# STM32F429IGT6.net
KiCad netlist of a schematic drawn in Altium Designer
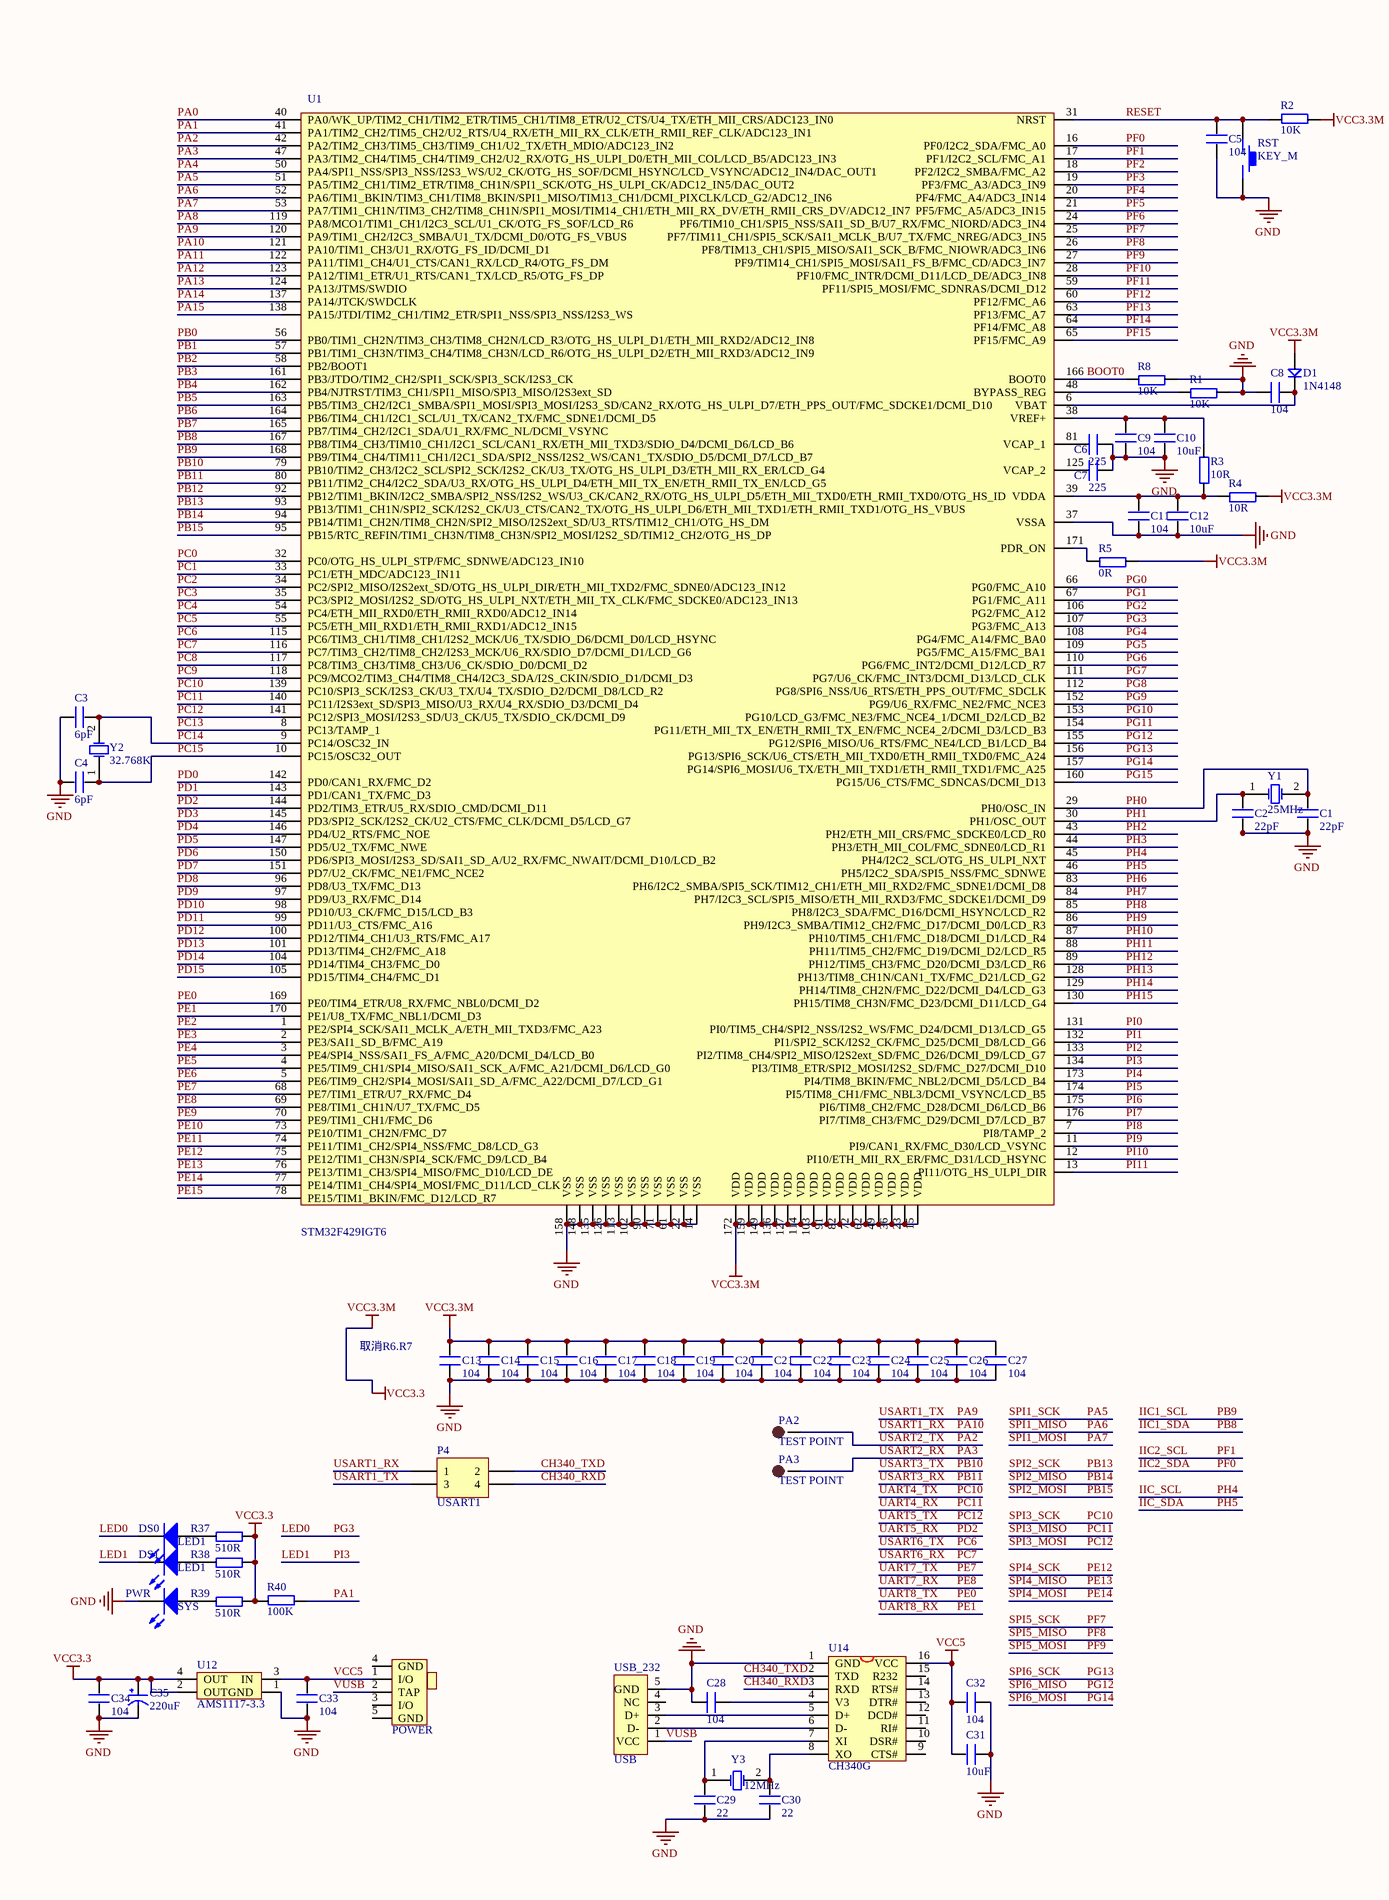
[diagram p0: STM32F429IGT6.SchDoc, left]
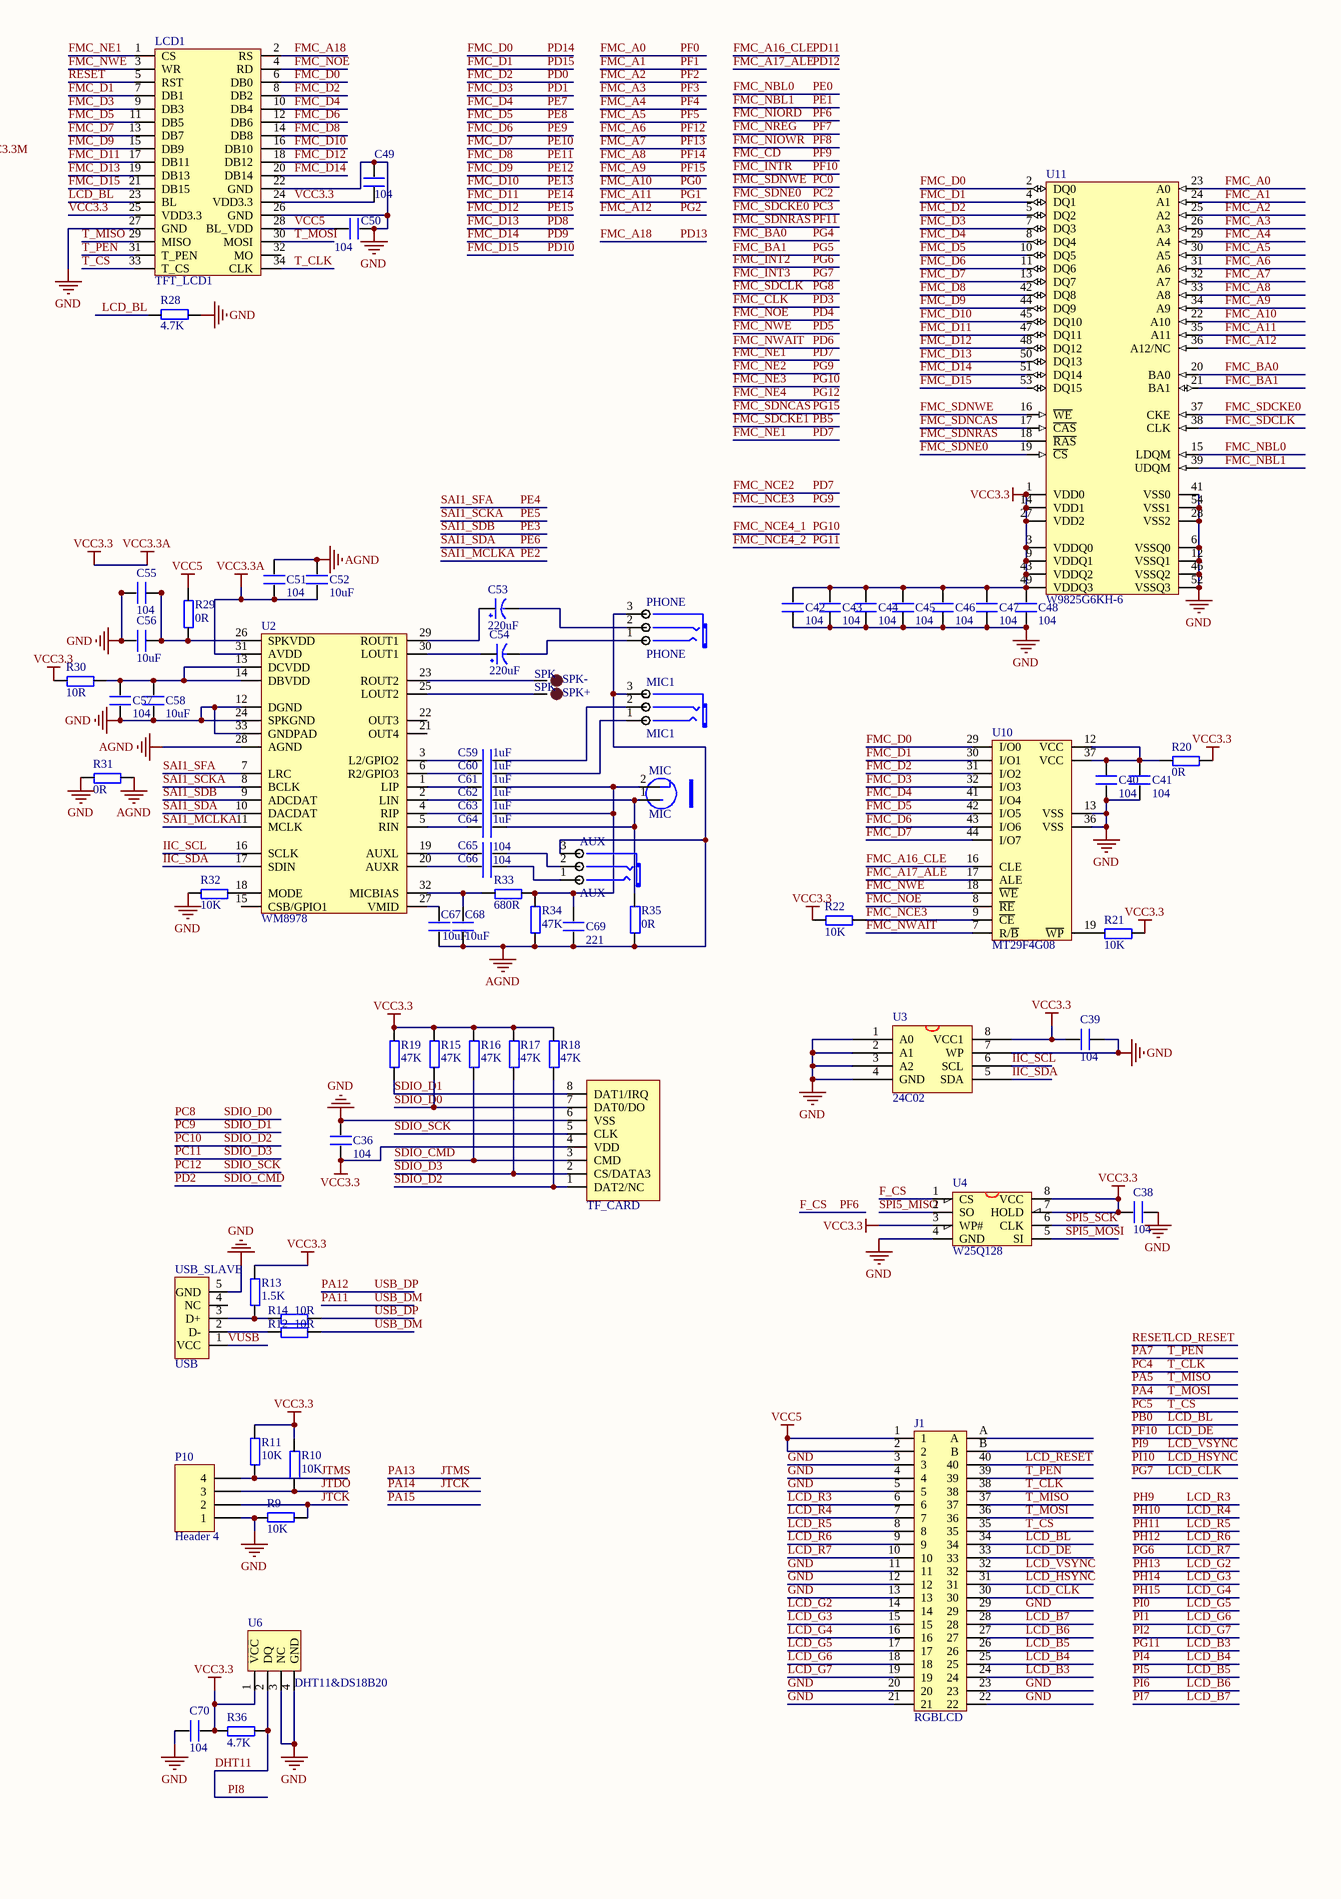
[diagram p1: STM32F429IGT6.SchDoc, right]

(export (version "E")
  (design (tool "Eeschema 10.0.6"))
  (components
    (comp (ref "AUX")
      (value "AUX")
      (footprint "PHONE_ST")
      (libsource (lib "阿波罗STM32F4&F7&H7底板封装库") (part "PHONE_M"))
    )
    (comp (ref "C1")
      (value "22pF")
      (footprint "C 0603_M")
      (libsource (lib "WarShip V3 STM32103封装库") (part "C"))
    )
    (comp (ref "C2")
      (value "22pF")
      (footprint "C 0603_M")
      (libsource (lib "WarShip V3 STM32103封装库") (part "C"))
    )
    (comp (ref "C3")
      (value "6pF")
      (footprint "C 0603_M")
      (libsource (lib "WarShip V3 STM32103封装库") (part "C"))
    )
    (comp (ref "C4")
      (value "6pF")
      (footprint "C 0603_M")
      (libsource (lib "WarShip V3 STM32103封装库") (part "C"))
    )
    (comp (ref "C5")
      (value "104")
      (footprint "C 0603_M")
      (libsource (lib "WarShip V3 STM32103封装库") (part "C"))
    )
    (comp (ref "C6") (value "225") (footprint "C 0603_M") (libsource (lib "阿波罗STM32F4&F7底板封装库") (part "C")))
    (comp (ref "C7") (value "225") (footprint "C 0603_M") (libsource (lib "阿波罗STM32F4&F7底板封装库") (part "C")))
    (comp (ref "C8") (value "104") (footprint "C 0603_M") (libsource (lib "阿波罗STM32F4&F7底板封装库") (part "C")))
    (comp (ref "C9") (value "104") (footprint "C 0603_M") (libsource (lib "阿波罗STM32F4&F7底板封装库") (part "C")))
    (comp (ref "C10") (value "10uF") (footprint "C 0603_M") (libsource (lib "阿波罗STM32F4&F7底板封装库") (part "C")))
    (comp (ref "C11") (value "104") (footprint "C 0603_M") (libsource (lib "阿波罗STM32F4&F7底板封装库") (part "C")))
    (comp (ref "C12") (value "10uF") (footprint "C 0603_M") (libsource (lib "阿波罗STM32F4&F7底板封装库") (part "C")))
    (comp (ref "C13") (value "104") (footprint "C 0603_M") (libsource (lib "STM32F429核心板封装库") (part "C")))
    (comp (ref "C14") (value "104") (footprint "C 0603_M") (libsource (lib "STM32F429核心板封装库") (part "C")))
    (comp (ref "C15") (value "104") (footprint "C 0603_M") (libsource (lib "STM32F429核心板封装库") (part "C")))
    (comp (ref "C16") (value "104") (footprint "C 0603_M") (libsource (lib "STM32F429核心板封装库") (part "C")))
    (comp (ref "C17") (value "104") (footprint "C 0603_M") (libsource (lib "STM32F429核心板封装库") (part "C")))
    (comp (ref "C18") (value "104") (footprint "C 0603_M") (libsource (lib "STM32F429核心板封装库") (part "C")))
    (comp (ref "C19") (value "104") (footprint "C 0603_M") (libsource (lib "STM32F429核心板封装库") (part "C")))
    (comp (ref "C20") (value "104") (footprint "C 0603_M") (libsource (lib "STM32F429核心板封装库") (part "C")))
    (comp (ref "C21") (value "104") (footprint "C 0603_M") (libsource (lib "STM32F429核心板封装库") (part "C")))
    (comp (ref "C22") (value "104") (footprint "C 0603_M") (libsource (lib "STM32F429核心板封装库") (part "C")))
    (comp (ref "C23") (value "104") (footprint "C 0603_M") (libsource (lib "STM32F429核心板封装库") (part "C")))
    (comp (ref "C24") (value "104") (footprint "C 0603_M") (libsource (lib "STM32F429核心板封装库") (part "C")))
    (comp (ref "C25") (value "104") (footprint "C 0603_M") (libsource (lib "STM32F429核心板封装库") (part "C")))
    (comp (ref "C26") (value "104") (footprint "C 0603_M") (libsource (lib "STM32F429核心板封装库") (part "C")))
    (comp (ref "C27") (value "104") (footprint "C 0603_M") (libsource (lib "STM32F429核心板封装库") (part "C")))
    (comp (ref "C28")
      (value "104")
      (footprint "C 0603_M")
      (libsource (lib "WarShip V3 STM32103封装库") (part "C"))
    )
    (comp (ref "C29")
      (value "22")
      (footprint "C 0603_M")
      (libsource (lib "WarShip V3 STM32103封装库") (part "C"))
    )
    (comp (ref "C30")
      (value "22")
      (footprint "C 0603_M")
      (libsource (lib "WarShip V3 STM32103封装库") (part "C"))
    )
    (comp (ref "C31")
      (value "10uF")
      (footprint "C 0603_M")
      (libsource (lib "WarShip V3 STM32103封装库") (part "C"))
    )
    (comp (ref "C32")
      (value "104")
      (footprint "C 0603_M")
      (libsource (lib "WarShip V3 STM32103封装库") (part "C"))
    )
    (comp (ref "C33")
      (value "104")
      (footprint "C 0603_M")
      (libsource (lib "WarShip V3 STM32103封装库") (part "C"))
    )
    (comp (ref "C34")
      (value "104")
      (footprint "C 0603_M")
      (libsource (lib "WarShip V3 STM32103封装库") (part "C"))
    )
    (comp (ref "C35")
      (value "220uF")
      (footprint "CT 6*6 - C")
      (libsource (lib "WarShip V3 STM32103封装库") (part "CAP"))
    )
    (comp (ref "C36")
      (value "104")
      (footprint "C 0603_M")
      (libsource (lib "WarShip V3 STM32103封装库") (part "C"))
    )
    (comp (ref "C38")
      (value "104")
      (footprint "C 0603_M")
      (libsource (lib "WarShip V3 STM32103封装库") (part "C"))
    )
    (comp (ref "C39")
      (value "104")
      (footprint "C 0603_M")
      (libsource (lib "WarShip V3 STM32103封装库") (part "C"))
    )
    (comp (ref "C40")
      (value "104")
      (footprint "C 0603_M")
      (libsource (lib "WarShip V3 STM32103封装库") (part "C"))
    )
    (comp (ref "C41")
      (value "104")
      (footprint "C 0603_M")
      (libsource (lib "WarShip V3 STM32103封装库") (part "C"))
    )
    (comp (ref "C42")
      (value "104")
      (footprint "C 0603_M")
      (libsource (lib "WarShip V3 STM32103封装库") (part "C"))
    )
    (comp (ref "C43")
      (value "104")
      (footprint "C 0603_M")
      (libsource (lib "WarShip V3 STM32103封装库") (part "C"))
    )
    (comp (ref "C44")
      (value "104")
      (footprint "C 0603_M")
      (libsource (lib "WarShip V3 STM32103封装库") (part "C"))
    )
    (comp (ref "C45")
      (value "104")
      (footprint "C 0603_M")
      (libsource (lib "WarShip V3 STM32103封装库") (part "C"))
    )
    (comp (ref "C46")
      (value "104")
      (footprint "C 0603_M")
      (libsource (lib "WarShip V3 STM32103封装库") (part "C"))
    )
    (comp (ref "C47")
      (value "104")
      (footprint "C 0603_M")
      (libsource (lib "WarShip V3 STM32103封装库") (part "C"))
    )
    (comp (ref "C48")
      (value "104")
      (footprint "C 0603_M")
      (libsource (lib "WarShip V3 STM32103封装库") (part "C"))
    )
    (comp (ref "C49") (value "104") (footprint "C 0603_M") (libsource (lib "MYCOMLIB") (part "C")))
    (comp (ref "C50") (value "104") (footprint "C 0603_M") (libsource (lib "MYCOMLIB") (part "C")))
    (comp (ref "C51") (value "104") (footprint "C 0603_M") (libsource (lib "阿波罗STM32F4&F7底板封装库") (part "C")))
    (comp (ref "C52") (value "10uF") (footprint "C 0603_M") (libsource (lib "阿波罗STM32F4&F7底板封装库") (part "C")))
    (comp (ref "C53")
      (value "220uF")
      (footprint "cc4*5.4")
      (libsource (lib "阿波罗STM32F4&F7底板封装库") (part "CAP"))
    )
    (comp (ref "C54")
      (value "220uF")
      (footprint "cc4*5.4")
      (libsource (lib "阿波罗STM32F4&F7底板封装库") (part "CAP"))
    )
    (comp (ref "C55") (value "104") (footprint "C 0603_M") (libsource (lib "阿波罗STM32F4&F7底板封装库") (part "C")))
    (comp (ref "C56") (value "10uF") (footprint "C 0603_M") (libsource (lib "阿波罗STM32F4&F7底板封装库") (part "C")))
    (comp (ref "C57") (value "104") (footprint "C 0603_M") (libsource (lib "阿波罗STM32F4&F7底板封装库") (part "C")))
    (comp (ref "C58") (value "10uF") (footprint "C 0603_M") (libsource (lib "阿波罗STM32F4&F7底板封装库") (part "C")))
    (comp (ref "C59") (value "1uF") (footprint "C 0603_M") (libsource (lib "阿波罗STM32F4&F7底板封装库") (part "C")))
    (comp (ref "C60") (value "1uF") (footprint "C 0603_M") (libsource (lib "阿波罗STM32F4&F7底板封装库") (part "C")))
    (comp (ref "C61") (value "1uF") (footprint "C 0603_M") (libsource (lib "阿波罗STM32F4&F7底板封装库") (part "C")))
    (comp (ref "C62") (value "1uF") (footprint "C 0603_M") (libsource (lib "阿波罗STM32F4&F7底板封装库") (part "C")))
    (comp (ref "C63") (value "1uF") (footprint "C 0603_M") (libsource (lib "阿波罗STM32F4&F7底板封装库") (part "C")))
    (comp (ref "C64") (value "1uF") (footprint "C 0603_M") (libsource (lib "阿波罗STM32F4&F7底板封装库") (part "C")))
    (comp (ref "C65") (value "104") (footprint "C 0603_M") (libsource (lib "阿波罗STM32F4&F7底板封装库") (part "C")))
    (comp (ref "C66") (value "104") (footprint "C 0603_M") (libsource (lib "阿波罗STM32F4&F7底板封装库") (part "C")))
    (comp (ref "C67") (value "10uF") (footprint "C 0603_M") (libsource (lib "阿波罗STM32F4&F7底板封装库") (part "C")))
    (comp (ref "C68") (value "10uF") (footprint "C 0603_M") (libsource (lib "阿波罗STM32F4&F7底板封装库") (part "C")))
    (comp (ref "C69") (value "221") (footprint "C 0603_M") (libsource (lib "阿波罗STM32F4&F7底板封装库") (part "C")))
    (comp (ref "C70")
      (value "104")
      (footprint "C 0603_M")
      (libsource (lib "WarShip V3 STM32103封装库") (part "C"))
    )
    (comp (ref "D1")
      (value "1N4148")
      (footprint "DIODE_SOP")
      (libsource (lib "WarShip V3 STM32103封装库") (part "D"))
    )
    (comp (ref "DS0")
      (value "LED1")
      (footprint "SMDLED")
      (description "Typical RED, GREEN, YELLOW, AMBER GaAs LED")
      (fields (field (name "PUBLISHER") "Altium Limited"))
      (libsource (lib "Miscellaneous Devices") (part "LED2"))
    )
    (comp (ref "DS1")
      (value "LED1")
      (footprint "SMDLED")
      (description "Typical RED, GREEN, YELLOW, AMBER GaAs LED")
      (fields (field (name "PUBLISHER") "Altium Limited"))
      (libsource (lib "Miscellaneous Devices") (part "LED2"))
    )
    (comp (ref "J1")
      (value "RGBLCD")
      (footprint "FPC-TOP40")
      (description "FPC-40P-0.5mm")
      (libsource (lib "STM32F429核心板封装库") (part "FPC-40"))
    )
    (comp (ref "LCD1")
      (value "TFT_LCD1")
      (footprint "DB2*17-3.5")
      (libsource (lib "3.5TFTLCD封装库") (part "TFT_LCD2"))
    )
    (comp (ref "MIC")
      (value "MIC")
      (footprint "MIC-6022")
      (libsource (lib "阿波罗STM32F4&F7&H7底板封装库") (part "MIC"))
    )
    (comp (ref "MIC1")
      (value "MIC1")
      (footprint "PHONE_ST")
      (libsource (lib "阿波罗STM32F4&F7&H7底板封装库") (part "PHONE_M"))
    )
    (comp (ref "P4")
      (value "USART1")
      (footprint "HDR2.54-LI-2x2P")
      (description "Header, 2-Pin, Dual row")
      (fields (field (name "PUBLISHER") "Altium Limited"))
      (libsource (lib "WarShip V3 STM32103封装库") (part "Header 2X2"))
    )
    (comp (ref "P10")
      (value "Header 4")
      (footprint "HDR2.54-LI-4P")
      (description "Header, 4-Pin")
      (fields (field (name "PUBLISHER") "Altium Limited"))
      (libsource (lib "WarShip V3 STM32103封装库") (part "Header 4"))
    )
    (comp (ref "PA2")
      (value "TEST POINT")
      (footprint "TP-1.5")
      (description "测试点")
      (libsource (lib "STM32F429核心板封装库") (part "TEST-POINT"))
    )
    (comp (ref "PA3")
      (value "TEST POINT")
      (footprint "TP-1.5")
      (description "测试点")
      (libsource (lib "STM32F429核心板封装库") (part "TEST-POINT"))
    )
    (comp (ref "PHONE")
      (value "PHONE")
      (footprint "PHONE_ST")
      (libsource (lib "阿波罗STM32F4&F7&H7底板封装库") (part "PHONE_M"))
    )
    (comp (ref "POWER")
      (value "BUTTON_DIP3")
      (footprint "BTN8.8*4.6")
      (description "拨动开关SS-12F44")
      (libsource (lib "Pandora_STM32L4_Board_V2.4") (part "BUTTON_DIP3"))
    )
    (comp (ref "PWR")
      (value "SYS")
      (footprint "SMDLED")
      (description "Typical RED, GREEN, YELLOW, AMBER GaAs LED")
      (fields (field (name "PUBLISHER") "Altium Limited"))
      (libsource (lib "Miscellaneous Devices") (part "LED2"))
    )
    (comp (ref "R1") (value "10K") (footprint "R 0603_M") (libsource (lib "阿波罗STM32F4&F7底板封装库") (part "R")))
    (comp (ref "R2")
      (value "10K")
      (footprint "R 0603_M")
      (libsource (lib "WarShip V3 STM32103封装库") (part "R"))
    )
    (comp (ref "R3") (value "10R") (footprint "R 0603_M") (libsource (lib "阿波罗STM32F4&F7底板封装库") (part "R")))
    (comp (ref "R4") (value "10R") (footprint "R 0603_M") (libsource (lib "阿波罗STM32F4&F7底板封装库") (part "R")))
    (comp (ref "R5") (value "0R") (footprint "R 0603_M") (libsource (lib "阿波罗STM32F4&F7底板封装库") (part "R")))
    (comp (ref "R8") (value "10K") (footprint "R 0603_M") (libsource (lib "阿波罗STM32F4&F7底板封装库") (part "R")))
    (comp (ref "R9")
      (value "10K")
      (footprint "R 0603_M")
      (libsource (lib "WarShip V3 STM32103封装库") (part "R"))
    )
    (comp (ref "R10")
      (value "10K")
      (footprint "R 0603_M")
      (libsource (lib "WarShip V3 STM32103封装库") (part "R"))
    )
    (comp (ref "R11")
      (value "10K")
      (footprint "R 0603_M")
      (libsource (lib "WarShip V3 STM32103封装库") (part "R"))
    )
    (comp (ref "R12")
      (value "10R")
      (footprint "R 0603_M")
      (libsource (lib "WarShip V3 STM32103封装库") (part "R"))
    )
    (comp (ref "R13")
      (value "1.5K")
      (footprint "R 0603_M")
      (libsource (lib "WarShip V3 STM32103封装库") (part "R"))
    )
    (comp (ref "R14")
      (value "10R")
      (footprint "R 0603_M")
      (libsource (lib "WarShip V3 STM32103封装库") (part "R"))
    )
    (comp (ref "R15")
      (value "47K")
      (footprint "R 0603_M")
      (libsource (lib "WarShip V3 STM32103封装库") (part "R"))
    )
    (comp (ref "R16")
      (value "47K")
      (footprint "R 0603_M")
      (libsource (lib "WarShip V3 STM32103封装库") (part "R"))
    )
    (comp (ref "R17")
      (value "47K")
      (footprint "R 0603_M")
      (libsource (lib "WarShip V3 STM32103封装库") (part "R"))
    )
    (comp (ref "R18")
      (value "47K")
      (footprint "R 0603_M")
      (libsource (lib "WarShip V3 STM32103封装库") (part "R"))
    )
    (comp (ref "R19")
      (value "47K")
      (footprint "R 0603_M")
      (libsource (lib "WarShip V3 STM32103封装库") (part "R"))
    )
    (comp (ref "R20")
      (value "0R")
      (footprint "R 0603_M")
      (libsource (lib "WarShip V3 STM32103封装库") (part "R"))
    )
    (comp (ref "R21")
      (value "10K")
      (footprint "R 0603_M")
      (libsource (lib "WarShip V3 STM32103封装库") (part "R"))
    )
    (comp (ref "R22")
      (value "10K")
      (footprint "R 0603_M")
      (libsource (lib "WarShip V3 STM32103封装库") (part "R"))
    )
    (comp (ref "R28") (value "4.7K") (footprint "R 0603_M") (libsource (lib "MYCOMLIB") (part "R")))
    (comp (ref "R29") (value "0R") (footprint "R 0603_M") (libsource (lib "阿波罗STM32F4&F7底板封装库") (part "R")))
    (comp (ref "R30") (value "10R") (footprint "R 0603_M") (libsource (lib "阿波罗STM32F4&F7底板封装库") (part "R")))
    (comp (ref "R31") (value "0R") (footprint "R 0603_M") (libsource (lib "阿波罗STM32F4&F7底板封装库") (part "R")))
    (comp (ref "R32") (value "10K") (footprint "R 0603_M") (libsource (lib "阿波罗STM32F4&F7底板封装库") (part "R")))
    (comp (ref "R33") (value "680R") (footprint "R 0603_M") (libsource (lib "阿波罗STM32F4&F7底板封装库") (part "R")))
    (comp (ref "R34") (value "47K") (footprint "R 0603_M") (libsource (lib "阿波罗STM32F4&F7底板封装库") (part "R")))
    (comp (ref "R35") (value "0R") (footprint "R 0603_M") (libsource (lib "阿波罗STM32F4&F7底板封装库") (part "R")))
    (comp (ref "R36")
      (value "4.7K")
      (footprint "R 0603_M")
      (libsource (lib "WarShip V3 STM32103封装库") (part "R"))
    )
    (comp (ref "R37") (value "510R") (footprint "R 0603_M") (libsource (lib "MYCOMLIB") (part "R")))
    (comp (ref "R38") (value "510R") (footprint "R 0603_M") (libsource (lib "MYCOMLIB") (part "R")))
    (comp (ref "R39") (value "510R") (footprint "R 0603_M") (libsource (lib "MYCOMLIB") (part "R")))
    (comp (ref "R40") (value "100K") (footprint "R 0603_M") (libsource (lib "MYCOMLIB") (part "R")))
    (comp (ref "RST")
      (value "KEY_M")
      (footprint "TSW SMD-3*6*2.5")
      (libsource (lib "STM32F429核心板封装库") (part "KEY_M"))
    )
    (comp (ref "SPK+")
      (value "SPK")
      (footprint "TP-1.5")
      (description "测试点")
      (libsource (lib "STM32F429核心板封装库") (part "TEST-POINT"))
    )
    (comp (ref "SPK-")
      (value "SPK")
      (footprint "TP-1.5")
      (description "测试点")
      (libsource (lib "STM32F429核心板封装库") (part "TEST-POINT"))
    )
    (comp (ref "TF_CARD")
      (value "SD-MICRO-TF")
      (footprint "SD-MICRO-TF")
      (description "SD,MICRO,TF")
      (libsource (lib "Pandora_STM32L4_Board_V2.4") (part "SD-MICRO-TF"))
    )
    (comp (ref "U1")
      (value "STM32F429IGT6")
      (footprint "LQFP176")
      (libsource (lib "STM32F429核心板封装库") (part "STM32F429IGT6"))
    )
    (comp (ref "U2")
      (value "WM8978")
      (footprint "qfn32")
      (description "24bit ADC&DAC")
      (libsource (lib "STM32H743") (part "WM8978"))
    )
    (comp (ref "U3")
      (value "24C02")
      (footprint "SOP8_M")
      (libsource (lib "WarShip V3 STM32103封装库") (part "24C256"))
    )
    (comp (ref "U4")
      (value "W25Q128")
      (footprint "SOIC-8")
      (description "W25X16;SST25VF016;MX25L1605")
      (libsource (lib "WarShip V3 STM32103封装库") (part "W25X16"))
    )
    (comp (ref "U6")
      (value "DHT11&DS18B20")
      (footprint "DHT11")
      (description "数字温湿度传感器")
      (libsource (lib "WarShip V3 STM32103封装库") (part "DHT11"))
    )
    (comp (ref "U10")
      (value "MT29F4G08")
      (footprint "TSOP48")
      (description "256MB NAND FLASH")
      (libsource (lib "STM32F429核心板封装库") (part "K9F2G08U0C"))
    )
    (comp (ref "U11")
      (value "W9825G6KH-6")
      (footprint "TSOP54")
      (description "32MB SDRAM")
      (libsource (lib "STM32F429核心板封装库") (part "IS42S16160B"))
    )
    (comp (ref "U12")
      (value "AMS1117-3.3")
      (footprint "AMS1117")
      (libsource (lib "WarShip V3 STM32103封装库") (part "AMS1117"))
    )
    (comp (ref "U14")
      (value "CH340G")
      (footprint "SOP16_M")
      (description "USB2UART")
      (libsource (lib "WarShip V3 STM32103封装库") (part "CH340G"))
    )
    (comp (ref "USB_232")
      (value "USB")
      (footprint "USB-MINI-A")
      (libsource (lib "WarShip V3 STM32103封装库") (part "USB5"))
    )
    (comp (ref "USB_SLAVE")
      (value "USB")
      (footprint "USB-MINI-A")
      (libsource (lib "WarShip V3 STM32103封装库") (part "USB5"))
    )
    (comp (ref "Y1")
      (value "25MHz")
      (footprint "OSC HC-49S")
      (description "Crystal Oscillator")
      (fields (field (name "PUBLISHER") "Altium Limited"))
      (libsource (lib "WarShip V3 STM32103封装库") (part "XTAL"))
    )
    (comp (ref "Y2")
      (value "32.768K")
      (footprint "OSC-2x6-WI-A")
      (description "Crystal Oscillator")
      (fields (field (name "PUBLISHER") "Altium Limited"))
      (libsource (lib "WarShip V3 STM32103封装库") (part "XTAL"))
    )
    (comp (ref "Y3")
      (value "12MHz")
      (footprint "OSC HC-49S")
      (description "Crystal Oscillator")
      (fields (field (name "PUBLISHER") "Altium Limited"))
      (libsource (lib "WarShip V3 STM32103封装库") (part "XTAL"))
    )
  )
  (nets
    (net (code "1") (name "/BOOT0") (class "Default")
      (node (ref "R8") (pin "1") (pintype "passive"))
      (node (ref "U1") (pin "166") (pinfunction "BOOT0_166") (pintype "passive"))
    )
    (net (code "2") (name "/CH340_RXD") (class "Default")
      (node (ref "P4") (pin "4") (pinfunction "4_4") (pintype "passive"))
      (node (ref "U14") (pin "3") (pinfunction "RXD_3") (pintype "passive"))
    )
    (net (code "3") (name "/CH340_TXD") (class "Default")
      (node (ref "P4") (pin "2") (pinfunction "2_2") (pintype "passive"))
      (node (ref "U14") (pin "2") (pinfunction "TXD_2") (pintype "passive"))
    )
    (net (code "4") (name "/DHT11") (class "Default")
      (node (ref "R36") (pin "2") (pintype "passive"))
      (node (ref "U1") (pin "7") (pinfunction "PI8/TAMP_2_7") (pintype "passive"))
      (node (ref "U6") (pin "2") (pinfunction "DQ_2") (pintype "passive"))
    )
    (net (code "5") (name "/FMC_A0") (class "Default")
      (node (ref "U1") (pin "16") (pinfunction "PF0/I2C2_SDA/FMC_A0_16") (pintype "passive"))
      (node (ref "U11") (pin "23") (pinfunction "A0_23") (pintype "input"))
    )
    (net (code "6") (name "/FMC_A1") (class "Default")
      (node (ref "U1") (pin "17") (pinfunction "PF1/I2C2_SCL/FMC_A1_17") (pintype "passive"))
      (node (ref "U11") (pin "24") (pinfunction "A1_24") (pintype "input"))
    )
    (net (code "7") (name "/FMC_A2") (class "Default")
      (node (ref "U1") (pin "18") (pinfunction "PF2/I2C2_SMBA/FMC_A2_18") (pintype "passive"))
      (node (ref "U11") (pin "25") (pinfunction "A2_25") (pintype "input"))
    )
    (net (code "8") (name "/FMC_A3") (class "Default")
      (node (ref "U1") (pin "19") (pinfunction "PF3/FMC_A3/ADC3_IN9_19") (pintype "passive"))
      (node (ref "U11") (pin "26") (pinfunction "A3_26") (pintype "input"))
    )
    (net (code "9") (name "/FMC_A4") (class "Default")
      (node (ref "U1") (pin "20") (pinfunction "PF4/FMC_A4/ADC3_IN14_20") (pintype "passive"))
      (node (ref "U11") (pin "29") (pinfunction "A4_29") (pintype "input"))
    )
    (net (code "10") (name "/FMC_A5") (class "Default")
      (node (ref "U1") (pin "21") (pinfunction "PF5/FMC_A5/ADC3_IN15_21") (pintype "passive"))
      (node (ref "U11") (pin "30") (pinfunction "A5_30") (pintype "input"))
    )
    (net (code "11") (name "/FMC_A6") (class "Default")
      (node (ref "U1") (pin "60") (pinfunction "PF12/FMC_A6_60") (pintype "passive"))
      (node (ref "U11") (pin "31") (pinfunction "A6_31") (pintype "input"))
    )
    (net (code "12") (name "/FMC_A7") (class "Default")
      (node (ref "U1") (pin "63") (pinfunction "PF13/FMC_A7_63") (pintype "passive"))
      (node (ref "U11") (pin "32") (pinfunction "A7_32") (pintype "input"))
    )
    (net (code "13") (name "/FMC_A8") (class "Default")
      (node (ref "U1") (pin "64") (pinfunction "PF14/FMC_A8_64") (pintype "passive"))
      (node (ref "U11") (pin "33") (pinfunction "A8_33") (pintype "input"))
    )
    (net (code "14") (name "/FMC_A9") (class "Default")
      (node (ref "U1") (pin "65") (pinfunction "PF15/FMC_A9_65") (pintype "passive"))
      (node (ref "U11") (pin "34") (pinfunction "A9_34") (pintype "input"))
    )
    (net (code "15") (name "/FMC_A10") (class "Default")
      (node (ref "U1") (pin "66") (pinfunction "PG0/FMC_A10_66") (pintype "passive"))
      (node (ref "U11") (pin "22") (pinfunction "A10_22") (pintype "input"))
    )
    (net (code "16") (name "/FMC_A11") (class "Default")
      (node (ref "U1") (pin "67") (pinfunction "PG1/FMC_A11_67") (pintype "passive"))
      (node (ref "U11") (pin "35") (pinfunction "A11_35") (pintype "input"))
    )
    (net (code "17") (name "/FMC_A12") (class "Default")
      (node (ref "U1") (pin "106") (pinfunction "PG2/FMC_A12_106") (pintype "passive"))
      (node (ref "U11") (pin "36") (pinfunction "A12/NC_36") (pintype "input"))
    )
    (net (code "18") (name "/FMC_A16_CLE") (class "Default")
      (node (ref "U1") (pin "99") (pinfunction "PD11/U3_CTS/FMC_A16_99") (pintype "passive"))
      (node (ref "U10") (pin "16") (pinfunction "CLE_16") (pintype "passive"))
    )
    (net (code "19") (name "/FMC_A17_ALE") (class "Default")
      (node (ref "U1") (pin "100") (pinfunction "PD12/TIM4_CH1/U3_RTS/FMC_A17_100") (pintype "passive"))
      (node (ref "U10") (pin "17") (pinfunction "ALE_17") (pintype "passive"))
    )
    (net (code "20") (name "/FMC_A18") (class "Default")
      (node (ref "LCD1") (pin "2") (pinfunction "RS_2") (pintype "passive"))
      (node (ref "U1") (pin "101") (pinfunction "PD13/TIM4_CH2/FMC_A18_101") (pintype "passive"))
    )
    (net (code "21") (name "/FMC_BA0") (class "Default")
      (node (ref "U1") (pin "108") (pinfunction "PG4/FMC_A14/FMC_BA0_108") (pintype "passive"))
      (node (ref "U11") (pin "20") (pinfunction "BA0_20") (pintype "input"))
    )
    (net (code "22") (name "/FMC_BA1") (class "Default")
      (node (ref "U1") (pin "109") (pinfunction "PG5/FMC_A15/FMC_BA1_109") (pintype "passive"))
      (node (ref "U11") (pin "21") (pinfunction "BA1_21") (pintype "bidirectional"))
    )
    (net (code "23") (name "/FMC_CD") (class "Default")
      (node (ref "U1") (pin "27") (pinfunction "PF9/TIM14_CH1/SPI5_MOSI/SAI1_FS_B/FMC_CD/ADC3_IN7_27") (pintype "passive"))
      (node (ref "U4") (pin "5") (pinfunction "SI_5") (pintype "passive"))
    )
    (net (code "24") (name "/FMC_CLK") (class "Default")
      (node (ref "U1") (pin "145") (pinfunction "PD3/SPI2_SCK/I2S2_CK/U2_CTS/FMC_CLK/DCMI_D5/LCD_G7_145") (pintype "passive"))
    )
    (net (code "25") (name "/FMC_D0") (class "Default")
      (node (ref "LCD1") (pin "6") (pinfunction "DB0_6") (pintype "passive"))
      (node (ref "U1") (pin "104") (pinfunction "PD14/TIM4_CH3/FMC_D0_104") (pintype "passive"))
      (node (ref "U10") (pin "29") (pinfunction "I/O0_29") (pintype "passive"))
      (node (ref "U11") (pin "2") (pinfunction "DQ0_2") (pintype "bidirectional"))
    )
    (net (code "26") (name "/FMC_D1") (class "Default")
      (node (ref "LCD1") (pin "7") (pinfunction "DB1_7") (pintype "passive"))
      (node (ref "U1") (pin "105") (pinfunction "PD15/TIM4_CH4/FMC_D1_105") (pintype "passive"))
      (node (ref "U10") (pin "30") (pinfunction "I/O1_30") (pintype "passive"))
      (node (ref "U11") (pin "4") (pinfunction "DQ1_4") (pintype "bidirectional"))
    )
    (net (code "27") (name "/FMC_D2") (class "Default")
      (node (ref "LCD1") (pin "8") (pinfunction "DB2_8") (pintype "passive"))
      (node (ref "U1") (pin "142") (pinfunction "PD0/CAN1_RX/FMC_D2_142") (pintype "passive"))
      (node (ref "U10") (pin "31") (pinfunction "I/O2_31") (pintype "passive"))
      (node (ref "U11") (pin "5") (pinfunction "DQ2_5") (pintype "bidirectional"))
    )
    (net (code "28") (name "/FMC_D3") (class "Default")
      (node (ref "LCD1") (pin "9") (pinfunction "DB3_9") (pintype "passive"))
      (node (ref "U1") (pin "143") (pinfunction "PD1/CAN1_TX/FMC_D3_143") (pintype "passive"))
      (node (ref "U10") (pin "32") (pinfunction "I/O3_32") (pintype "passive"))
      (node (ref "U11") (pin "7") (pinfunction "DQ3_7") (pintype "bidirectional"))
    )
    (net (code "29") (name "/FMC_D4") (class "Default")
      (node (ref "LCD1") (pin "10") (pinfunction "DB4_10") (pintype "passive"))
      (node (ref "U1") (pin "68") (pinfunction "PE7/TIM1_ETR/U7_RX/FMC_D4_68") (pintype "passive"))
      (node (ref "U10") (pin "41") (pinfunction "I/O4_41") (pintype "passive"))
      (node (ref "U11") (pin "8") (pinfunction "DQ4_8") (pintype "bidirectional"))
    )
    (net (code "30") (name "/FMC_D5") (class "Default")
      (node (ref "LCD1") (pin "11") (pinfunction "DB5_11") (pintype "passive"))
      (node (ref "U1") (pin "69") (pinfunction "PE8/TIM1_CH1N/U7_TX/FMC_D5_69") (pintype "passive"))
      (node (ref "U10") (pin "42") (pinfunction "I/O5_42") (pintype "passive"))
      (node (ref "U11") (pin "10") (pinfunction "DQ5_10") (pintype "bidirectional"))
    )
    (net (code "31") (name "/FMC_D6") (class "Default")
      (node (ref "LCD1") (pin "12") (pinfunction "DB6_12") (pintype "passive"))
      (node (ref "U1") (pin "70") (pinfunction "PE9/TIM1_CH1/FMC_D6_70") (pintype "passive"))
      (node (ref "U10") (pin "43") (pinfunction "I/O6_43") (pintype "passive"))
      (node (ref "U11") (pin "11") (pinfunction "DQ6_11") (pintype "bidirectional"))
    )
    (net (code "32") (name "/FMC_D7") (class "Default")
      (node (ref "LCD1") (pin "13") (pinfunction "DB7_13") (pintype "passive"))
      (node (ref "U1") (pin "73") (pinfunction "PE10/TIM1_CH2N/FMC_D7_73") (pintype "passive"))
      (node (ref "U10") (pin "44") (pinfunction "I/O7_44") (pintype "passive"))
      (node (ref "U11") (pin "13") (pinfunction "DQ7_13") (pintype "bidirectional"))
    )
    (net (code "33") (name "/FMC_D8") (class "Default")
      (node (ref "LCD1") (pin "14") (pinfunction "DB8_14") (pintype "passive"))
      (node (ref "U1") (pin "74") (pinfunction "PE11/TIM1_CH2/SPI4_NSS/FMC_D8/LCD_G3_74") (pintype "passive"))
      (node (ref "U11") (pin "42") (pinfunction "DQ8_42") (pintype "bidirectional"))
    )
    (net (code "34") (name "/FMC_D9") (class "Default")
      (node (ref "LCD1") (pin "15") (pinfunction "DB9_15") (pintype "passive"))
      (node (ref "U1") (pin "75") (pinfunction "PE12/TIM1_CH3N/SPI4_SCK/FMC_D9/LCD_B4_75") (pintype "passive"))
      (node (ref "U11") (pin "44") (pinfunction "DQ9_44") (pintype "bidirectional"))
    )
    (net (code "35") (name "/FMC_D10") (class "Default")
      (node (ref "LCD1") (pin "16") (pinfunction "DB10_16") (pintype "passive"))
      (node (ref "U1") (pin "76") (pinfunction "PE13/TIM1_CH3/SPI4_MISO/FMC_D10/LCD_DE_76") (pintype "passive"))
      (node (ref "U11") (pin "45") (pinfunction "DQ10_45") (pintype "bidirectional"))
    )
    (net (code "36") (name "/FMC_D11") (class "Default")
      (node (ref "LCD1") (pin "17") (pinfunction "DB11_17") (pintype "passive"))
      (node (ref "U1") (pin "77") (pinfunction "PE14/TIM1_CH4/SPI4_MOSI/FMC_D11/LCD_CLK_77") (pintype "passive"))
      (node (ref "U11") (pin "47") (pinfunction "DQ11_47") (pintype "bidirectional"))
    )
    (net (code "37") (name "/FMC_D12") (class "Default")
      (node (ref "LCD1") (pin "18") (pinfunction "DB12_18") (pintype "passive"))
      (node (ref "U1") (pin "78") (pinfunction "PE15/TIM1_BKIN/FMC_D12/LCD_R7_78") (pintype "passive"))
      (node (ref "U11") (pin "48") (pinfunction "DQ12_48") (pintype "bidirectional"))
    )
    (net (code "38") (name "/FMC_D13") (class "Default")
      (node (ref "LCD1") (pin "19") (pinfunction "DB13_19") (pintype "passive"))
      (node (ref "U1") (pin "96") (pinfunction "PD8/U3_TX/FMC_D13_96") (pintype "passive"))
      (node (ref "U11") (pin "50") (pinfunction "DQ13_50") (pintype "bidirectional"))
    )
    (net (code "39") (name "/FMC_D14") (class "Default")
      (node (ref "LCD1") (pin "20") (pinfunction "DB14_20") (pintype "passive"))
      (node (ref "U1") (pin "97") (pinfunction "PD9/U3_RX/FMC_D14_97") (pintype "passive"))
      (node (ref "U11") (pin "51") (pinfunction "DQ14_51") (pintype "bidirectional"))
    )
    (net (code "40") (name "/FMC_D15") (class "Default")
      (node (ref "LCD1") (pin "21") (pinfunction "DB15_21") (pintype "passive"))
      (node (ref "U1") (pin "98") (pinfunction "PD10/U3_CK/FMC_D15/LCD_B3_98") (pintype "passive"))
      (node (ref "U11") (pin "53") (pinfunction "DQ15_53") (pintype "bidirectional"))
    )
    (net (code "41") (name "/FMC_INT2") (class "Default")
      (node (ref "J1") (pin "10") (pinfunction "10_10") (pintype "passive"))
      (node (ref "U1") (pin "110") (pinfunction "PG6/FMC_INT2/DCMI_D12/LCD_R7_110") (pintype "passive"))
    )
    (net (code "42") (name "/FMC_INT3") (class "Default")
      (node (ref "J1") (pin "30") (pinfunction "30_30") (pintype "passive"))
      (node (ref "U1") (pin "111") (pinfunction "PG7/U6_CK/FMC_INT3/DCMI_D13/LCD_CLK_111") (pintype "passive"))
    )
    (net (code "43") (name "/FMC_INTR") (class "Default")
      (node (ref "J1") (pin "33") (pinfunction "33_33") (pintype "passive"))
      (node (ref "U1") (pin "28") (pinfunction "PF10/FMC_INTR/DCMI_D11/LCD_DE/ADC3_IN8_28") (pintype "passive"))
    )
    (net (code "44") (name "/FMC_NBL0") (class "Default")
      (node (ref "U1") (pin "169") (pinfunction "PE0/TIM4_ETR/U8_RX/FMC_NBL0/DCMI_D2_169") (pintype "passive"))
      (node (ref "U11") (pin "15") (pinfunction "LDQM_15") (pintype "input"))
    )
    (net (code "45") (name "/FMC_NBL1") (class "Default")
      (node (ref "U1") (pin "170") (pinfunction "PE1/U8_TX/FMC_NBL1/DCMI_D3_170") (pintype "passive"))
      (node (ref "U11") (pin "39") (pinfunction "UDQM_39") (pintype "input"))
    )
    (net (code "46") (name "/FMC_NCE2") (class "Default")
      (node (ref "LCD1") (pin "1") (pinfunction "CS_1") (pintype "passive"))
      (node (ref "U1") (pin "151") (pinfunction "PD7/U2_CK/FMC_NE1/FMC_NCE2_151") (pintype "passive"))
    )
    (net (code "47") (name "/FMC_NCE3") (class "Default")
      (node (ref "R22") (pin "2") (pintype "passive"))
      (node (ref "U1") (pin "152") (pinfunction "PG9/U6_RX/FMC_NE2/FMC_NCE3_152") (pintype "passive"))
      (node (ref "U10") (pin "9") (pinfunction "~{CE}_9") (pintype "passive"))
    )
    (net (code "48") (name "/FMC_NCE4_1") (class "Default")
      (node (ref "U1") (pin "153") (pinfunction "PG10/LCD_G3/FMC_NE3/FMC_NCE4_1/DCMI_D2/LCD_B2_153") (pintype "passive"))
    )
    (net (code "49") (name "/FMC_NCE4_2") (class "Default")
      (node (ref "J1") (pin "24") (pinfunction "24_24") (pintype "passive"))
      (node (ref "U1") (pin "154") (pinfunction "PG11/ETH_MII_TX_EN/ETH_RMII_TX_EN/FMC_NCE4_2/DCMI_D3/LCD_B3_154") (pintype "passive"))
    )
    (net (code "50") (name "/FMC_NE4") (class "Default")
      (node (ref "U1") (pin "155") (pinfunction "PG12/SPI6_MISO/U6_RTS/FMC_NE4/LCD_B1/LCD_B4_155") (pintype "passive"))
    )
    (net (code "51") (name "/FMC_NIORD") (class "Default")
      (node (ref "U1") (pin "24") (pinfunction "PF6/TIM10_CH1/SPI5_NSS/SAI1_SD_B/U7_RX/FMC_NIORD/ADC3_IN4_24") (pintype "passive"))
      (node (ref "U4") (pin "1") (pinfunction "CS_1") (pintype "passive"))
    )
    (net (code "52") (name "/FMC_NIOWR") (class "Default")
      (node (ref "U1") (pin "26") (pinfunction "PF8/TIM13_CH1/SPI5_MISO/SAI1_SCK_B/FMC_NIOWR/ADC3_IN6_26") (pintype "passive"))
      (node (ref "U4") (pin "2") (pinfunction "SO_2") (pintype "passive"))
    )
    (net (code "53") (name "/FMC_NOE") (class "Default")
      (node (ref "LCD1") (pin "4") (pinfunction "RD_4") (pintype "passive"))
      (node (ref "U1") (pin "146") (pinfunction "PD4/U2_RTS/FMC_NOE_146") (pintype "passive"))
      (node (ref "U10") (pin "8") (pinfunction "~{RE}_8") (pintype "passive"))
    )
    (net (code "54") (name "/FMC_NREG") (class "Default")
      (node (ref "U1") (pin "25") (pinfunction "PF7/TIM11_CH1/SPI5_SCK/SAI1_MCLK_B/U7_TX/FMC_NREG/ADC3_IN5_25") (pintype "passive"))
      (node (ref "U4") (pin "6") (pinfunction "CLK_6") (pintype "passive"))
    )
    (net (code "55") (name "/FMC_NWAIT") (class "Default")
      (node (ref "U1") (pin "150") (pinfunction "PD6/SPI3_MOSI/I2S3_SD/SAI1_SD_A/U2_RX/FMC_NWAIT/DCMI_D10/LCD_B2_150") (pintype "passive"))
      (node (ref "U10") (pin "7") (pinfunction "R/~{B}_7") (pintype "passive"))
    )
    (net (code "56") (name "/FMC_NWE") (class "Default")
      (node (ref "LCD1") (pin "3") (pinfunction "WR_3") (pintype "passive"))
      (node (ref "U1") (pin "147") (pinfunction "PD5/U2_TX/FMC_NWE_147") (pintype "passive"))
      (node (ref "U10") (pin "18") (pinfunction "~{WE}_18") (pintype "passive"))
    )
    (net (code "57") (name "/FMC_SDCKE0") (class "Default")
      (node (ref "U1") (pin "35") (pinfunction "PC3/SPI2_MOSI/I2S2_SD/OTG_HS_ULPI_NXT/ETH_MII_TX_CLK/FMC_SDCKE0/ADC123_IN13_35") (pintype "passive"))
      (node (ref "U11") (pin "37") (pinfunction "CKE_37") (pintype "input"))
    )
    (net (code "58") (name "/FMC_SDCKE1") (class "Default")
      (node (ref "U1") (pin "163") (pinfunction "PB5/TIM3_CH2/I2C1_SMBA/SPI1_MOSI/SPI3_MOSI/I2S3_SD/CAN2_RX/OTG_HS_ULPI_D7/ETH_PPS_OUT/FMC_SDCKE1/DCMI_D10_163") (pintype "passive"))
    )
    (net (code "59") (name "/FMC_SDCLK") (class "Default")
      (node (ref "U1") (pin "112") (pinfunction "PG8/SPI6_NSS/U6_RTS/ETH_PPS_OUT/FMC_SDCLK_112") (pintype "passive"))
      (node (ref "U11") (pin "38") (pinfunction "CLK_38") (pintype "input"))
    )
    (net (code "60") (name "/FMC_SDNCAS") (class "Default")
      (node (ref "U1") (pin "160") (pinfunction "PG15/U6_CTS/FMC_SDNCAS/DCMI_D13_160") (pintype "passive"))
      (node (ref "U11") (pin "17") (pinfunction "~{CAS}_17") (pintype "input"))
    )
    (net (code "61") (name "/FMC_SDNE0") (class "Default")
      (node (ref "U1") (pin "34") (pinfunction "PC2/SPI2_MISO/I2S2ext_SD/OTG_HS_ULPI_DIR/ETH_MII_TXD2/FMC_SDNE0/ADC123_IN12_34") (pintype "passive"))
      (node (ref "U11") (pin "19") (pinfunction "~{CS}_19") (pintype "input"))
    )
    (net (code "62") (name "/FMC_SDNRAS") (class "Default")
      (node (ref "U1") (pin "59") (pinfunction "PF11/SPI5_MOSI/FMC_SDNRAS/DCMI_D12_59") (pintype "passive"))
      (node (ref "U11") (pin "18") (pinfunction "~{RAS}_18") (pintype "passive"))
    )
    (net (code "63") (name "/FMC_SDNWE") (class "Default")
      (node (ref "U1") (pin "32") (pinfunction "PC0/OTG_HS_ULPI_STP/FMC_SDNWE/ADC123_IN10_32") (pintype "passive"))
      (node (ref "U11") (pin "16") (pinfunction "~{WE}_16") (pintype "input"))
    )
    (net (code "64") (name "/IIC1_SCL") (class "Default")
      (node (ref "U1") (pin "168") (pinfunction "PB9/TIM4_CH4/TIM11_CH1/I2C1_SDA/SPI2_NSS/I2S2_WS/CAN1_TX/SDIO_D5/DCMI_D7/LCD_B7_168") (pintype "passive"))
    )
    (net (code "65") (name "/IIC1_SDA") (class "Default")
      (node (ref "U1") (pin "167") (pinfunction "PB8/TIM4_CH3/TIM10_CH1/I2C1_SCL/CAN1_RX/ETH_MII_TXD3/SDIO_D4/DCMI_D6/LCD_B6_167") (pintype "passive"))
    )
    (net (code "66") (name "/IIC_SCL") (class "Default")
      (node (ref "U1") (pin "45") (pinfunction "PH4/I2C2_SCL/OTG_HS_ULPI_NXT_45") (pintype "passive"))
      (node (ref "U2") (pin "16") (pinfunction "SCLK_16") (pintype "passive"))
      (node (ref "U3") (pin "6") (pinfunction "SCL_6") (pintype "passive"))
    )
    (net (code "67") (name "/IIC_SDA") (class "Default")
      (node (ref "U1") (pin "46") (pinfunction "PH5/I2C2_SDA/SPI5_NSS/FMC_SDNWE_46") (pintype "passive"))
      (node (ref "U2") (pin "17") (pinfunction "SDIN_17") (pintype "passive"))
      (node (ref "U3") (pin "5") (pinfunction "SDA_5") (pintype "passive"))
    )
    (net (code "68") (name "/JTCK") (class "Default")
      (node (ref "P10") (pin "2") (pinfunction "2_2") (pintype "passive"))
      (node (ref "R9") (pin "1") (pintype "passive"))
      (node (ref "U1") (pin "137") (pinfunction "PA14/JTCK/SWDCLK_137") (pintype "passive"))
    )
    (net (code "69") (name "/JTDO") (class "Default")
      (node (ref "P10") (pin "3") (pinfunction "3_3") (pintype "passive"))
      (node (ref "R10") (pin "1") (pintype "passive"))
    )
    (net (code "70") (name "/JTMS") (class "Default")
      (node (ref "P10") (pin "4") (pinfunction "4_4") (pintype "passive"))
      (node (ref "R11") (pin "1") (pintype "passive"))
      (node (ref "U1") (pin "124") (pinfunction "PA13/JTMS/SWDIO_124") (pintype "passive"))
    )
    (net (code "71") (name "/LCD_B4") (class "Default")
      (node (ref "J1") (pin "25") (pinfunction "25_25") (pintype "passive"))
      (node (ref "U1") (pin "173") (pinfunction "PI4/TIM8_BKIN/FMC_NBL2/DCMI_D5/LCD_B4_173") (pintype "passive"))
    )
    (net (code "72") (name "/LCD_B5") (class "Default")
      (node (ref "J1") (pin "26") (pinfunction "26_26") (pintype "passive"))
      (node (ref "U1") (pin "174") (pinfunction "PI5/TIM8_CH1/FMC_NBL3/DCMI_VSYNC/LCD_B5_174") (pintype "passive"))
    )
    (net (code "73") (name "/LCD_B6") (class "Default")
      (node (ref "J1") (pin "27") (pinfunction "27_27") (pintype "passive"))
      (node (ref "U1") (pin "175") (pinfunction "PI6/TIM8_CH2/FMC_D28/DCMI_D6/LCD_B6_175") (pintype "passive"))
    )
    (net (code "74") (name "/LCD_B7") (class "Default")
      (node (ref "J1") (pin "28") (pinfunction "28_28") (pintype "passive"))
      (node (ref "U1") (pin "176") (pinfunction "PI7/TIM8_CH3/FMC_D29/DCMI_D7/LCD_B7_176") (pintype "passive"))
    )
    (net (code "75") (name "/LCD_BL") (class "Default")
      (node (ref "J1") (pin "34") (pinfunction "34_34") (pintype "passive"))
      (node (ref "LCD1") (pin "23") (pinfunction "BL_23") (pintype "passive"))
      (node (ref "R28") (pin "2") (pintype "passive"))
      (node (ref "U1") (pin "56") (pinfunction "PB0/TIM1_CH2N/TIM3_CH3/TIM8_CH2N/LCD_R3/OTG_HS_ULPI_D1/ETH_MII_RXD2/ADC12_IN8_56") (pintype "passive"))
    )
    (net (code "76") (name "/LCD_G2") (class "Default")
      (node (ref "J1") (pin "14") (pinfunction "14_14") (pintype "passive"))
      (node (ref "U1") (pin "128") (pinfunction "PH13/TIM8_CH1N/CAN1_TX/FMC_D21/LCD_G2_128") (pintype "passive"))
    )
    (net (code "77") (name "/LCD_G3") (class "Default")
      (node (ref "J1") (pin "15") (pinfunction "15_15") (pintype "passive"))
      (node (ref "U1") (pin "129") (pinfunction "PH14/TIM8_CH2N/FMC_D22/DCMI_D4/LCD_G3_129") (pintype "passive"))
    )
    (net (code "78") (name "/LCD_G4") (class "Default")
      (node (ref "J1") (pin "16") (pinfunction "16_16") (pintype "passive"))
      (node (ref "U1") (pin "130") (pinfunction "PH15/TIM8_CH3N/FMC_D23/DCMI_D11/LCD_G4_130") (pintype "passive"))
    )
    (net (code "79") (name "/LCD_G5") (class "Default")
      (node (ref "J1") (pin "17") (pinfunction "17_17") (pintype "passive"))
      (node (ref "U1") (pin "131") (pinfunction "PI0/TIM5_CH4/SPI2_NSS/I2S2_WS/FMC_D24/DCMI_D13/LCD_G5_131") (pintype "passive"))
    )
    (net (code "80") (name "/LCD_G6") (class "Default")
      (node (ref "J1") (pin "18") (pinfunction "18_18") (pintype "passive"))
      (node (ref "U1") (pin "132") (pinfunction "PI1/SPI2_SCK/I2S2_CK/FMC_D25/DCMI_D8/LCD_G6_132") (pintype "passive"))
    )
    (net (code "81") (name "/LCD_G7") (class "Default")
      (node (ref "J1") (pin "19") (pinfunction "19_19") (pintype "passive"))
      (node (ref "U1") (pin "133") (pinfunction "PI2/TIM8_CH4/SPI2_MISO/I2S2ext_SD/FMC_D26/DCMI_D9/LCD_G7_133") (pintype "passive"))
    )
    (net (code "82") (name "/LCD_HSYNC") (class "Default")
      (node (ref "J1") (pin "31") (pinfunction "31_31") (pintype "passive"))
      (node (ref "U1") (pin "12") (pinfunction "PI10/ETH_MII_RX_ER/FMC_D31/LCD_HSYNC_12") (pintype "passive"))
    )
    (net (code "83") (name "/LCD_R3") (class "Default")
      (node (ref "J1") (pin "6") (pinfunction "6_6") (pintype "passive"))
      (node (ref "U1") (pin "86") (pinfunction "PH9/I2C3_SMBA/TIM12_CH2/FMC_D17/DCMI_D0/LCD_R3_86") (pintype "passive"))
    )
    (net (code "84") (name "/LCD_R4") (class "Default")
      (node (ref "J1") (pin "7") (pinfunction "7_7") (pintype "passive"))
      (node (ref "U1") (pin "87") (pinfunction "PH10/TIM5_CH1/FMC_D18/DCMI_D1/LCD_R4_87") (pintype "passive"))
    )
    (net (code "85") (name "/LCD_R5") (class "Default")
      (node (ref "J1") (pin "8") (pinfunction "8_8") (pintype "passive"))
      (node (ref "U1") (pin "88") (pinfunction "PH11/TIM5_CH2/FMC_D19/DCMI_D2/LCD_R5_88") (pintype "passive"))
    )
    (net (code "86") (name "/LCD_R6") (class "Default")
      (node (ref "J1") (pin "9") (pinfunction "9_9") (pintype "passive"))
      (node (ref "U1") (pin "89") (pinfunction "PH12/TIM5_CH3/FMC_D20/DCMI_D3/LCD_R6_89") (pintype "passive"))
    )
    (net (code "87") (name "/LCD_RESET") (class "Default")
      (node (ref "C5") (pin "2") (pintype "passive"))
      (node (ref "J1") (pin "40") (pinfunction "40_40") (pintype "passive"))
      (node (ref "LCD1") (pin "5") (pinfunction "RST_5") (pintype "passive"))
      (node (ref "R2") (pin "2") (pintype "passive"))
      (node (ref "RST") (pin "1") (pinfunction "1_1") (pintype "passive"))
      (node (ref "U1") (pin "31") (pinfunction "NRST_31") (pintype "passive"))
    )
    (net (code "88") (name "/LCD_VSYNC") (class "Default")
      (node (ref "J1") (pin "32") (pinfunction "32_32") (pintype "passive"))
      (node (ref "U1") (pin "11") (pinfunction "PI9/CAN1_RX/FMC_D30/LCD_VSYNC_11") (pintype "passive"))
    )
    (net (code "89") (name "/LED0") (class "Default")
      (node (ref "DS0") (pin "2") (pinfunction "K_2") (pintype "passive"))
      (node (ref "U1") (pin "107") (pinfunction "PG3/FMC_A13_107") (pintype "passive"))
    )
    (net (code "90") (name "/LED1") (class "Default")
      (node (ref "DS1") (pin "2") (pinfunction "K_2") (pintype "passive"))
      (node (ref "U1") (pin "134") (pinfunction "PI3/TIM8_ETR/SPI2_MOSI/I2S2_SD/FMC_D27/DCMI_D10_134") (pintype "passive"))
    )
    (net (code "91") (name "/PA0") (class "Default")
      (node (ref "U1") (pin "40") (pinfunction "PA0/WK_UP/TIM2_CH1/TIM2_ETR/TIM5_CH1/TIM8_ETR/U2_CTS/U4_TX/ETH_MII_CRS/ADC123_IN0_40") (pintype "passive"))
    )
    (net (code "92") (name "/PA1") (class "Default")
      (node (ref "R40") (pin "1") (pintype "passive"))
      (node (ref "U1") (pin "41") (pinfunction "PA1/TIM2_CH2/TIM5_CH2/U2_RTS/U4_RX/ETH_MII_RX_CLK/ETH_RMII_REF_CLK/ADC123_IN1_41") (pintype "passive"))
    )
    (net (code "93") (name "/PA2") (class "Default")
      (node (ref "PA2") (pin "1") (pinfunction "1_1") (pintype "passive"))
      (node (ref "U1") (pin "42") (pinfunction "PA2/TIM2_CH3/TIM5_CH3/TIM9_CH1/U2_TX/ETH_MDIO/ADC123_IN2_42") (pintype "passive"))
    )
    (net (code "94") (name "/PA3") (class "Default")
      (node (ref "PA3") (pin "1") (pinfunction "1_1") (pintype "passive"))
      (node (ref "U1") (pin "47") (pinfunction "PA3/TIM2_CH4/TIM5_CH4/TIM9_CH2/U2_RX/OTG_HS_ULPI_D0/ETH_MII_COL/LCD_B5/ADC123_IN3_47") (pintype "passive"))
    )
    (net (code "95") (name "/PA4") (class "Default")
      (node (ref "J1") (pin "36") (pinfunction "36_36") (pintype "passive"))
      (node (ref "LCD1") (pin "30") (pinfunction "MOSI_30") (pintype "passive"))
      (node (ref "U1") (pin "50") (pinfunction "PA4/SPI1_NSS/SPI3_NSS/I2S3_WS/U2_CK/OTG_HS_SOF/DCMI_HSYNC/LCD_VSYNC/ADC12_IN4/DAC_OUT1_50") (pintype "passive"))
    )
    (net (code "96") (name "/PA5") (class "Default")
      (node (ref "J1") (pin "37") (pinfunction "37_37") (pintype "passive"))
      (node (ref "LCD1") (pin "29") (pinfunction "MISO_29") (pintype "passive"))
      (node (ref "U1") (pin "51") (pinfunction "PA5/TIM2_CH1/TIM2_ETR/TIM8_CH1N/SPI1_SCK/OTG_HS_ULPI_CK/ADC12_IN5/DAC_OUT2_51") (pintype "passive"))
    )
    (net (code "97") (name "/PA6") (class "Default")
      (node (ref "U1") (pin "52") (pinfunction "PA6/TIM1_BKIN/TIM3_CH1/TIM8_BKIN/SPI1_MISO/TIM13_CH1/DCMI_PIXCLK/LCD_G2/ADC12_IN6_52") (pintype "passive"))
    )
    (net (code "98") (name "/PA7") (class "Default")
      (node (ref "J1") (pin "39") (pinfunction "39_39") (pintype "passive"))
      (node (ref "LCD1") (pin "31") (pinfunction "T_PEN_31") (pintype "passive"))
      (node (ref "U1") (pin "53") (pinfunction "PA7/TIM1_CH1N/TIM3_CH2/TIM8_CH1N/SPI1_MOSI/TIM14_CH1/ETH_MII_RX_DV/ETH_RMII_CRS_DV/ADC12_IN7_53") (pintype "passive"))
    )
    (net (code "99") (name "/PA8") (class "Default")
      (node (ref "U1") (pin "119") (pinfunction "PA8/MCO1/TIM1_CH1/I2C3_SCL/U1_CK/OTG_FS_SOF/LCD_R6_119") (pintype "passive"))
    )
    (net (code "100") (name "/PA9") (class "Default")
      (node (ref "P4") (pin "3") (pinfunction "3_3") (pintype "passive"))
      (node (ref "U1") (pin "120") (pinfunction "PA9/TIM1_CH2/I2C3_SMBA/U1_TX/DCMI_D0/OTG_FS_VBUS_120") (pintype "passive"))
    )
    (net (code "101") (name "/PA10") (class "Default")
      (node (ref "P4") (pin "1") (pinfunction "1_1") (pintype "passive"))
      (node (ref "U1") (pin "121") (pinfunction "PA10/TIM1_CH3/U1_RX/OTG_FS_ID/DCMI_D1_121") (pintype "passive"))
    )
    (net (code "102") (name "/PA11") (class "Default")
      (node (ref "R12") (pin "2") (pintype "passive"))
      (node (ref "U1") (pin "122") (pinfunction "PA11/TIM1_CH4/U1_CTS/CAN1_RX/LCD_R4/OTG_FS_DM_122") (pintype "passive"))
    )
    (net (code "103") (name "/PA12") (class "Default")
      (node (ref "R14") (pin "2") (pintype "passive"))
      (node (ref "U1") (pin "123") (pinfunction "PA12/TIM1_ETR/U1_RTS/CAN1_TX/LCD_R5/OTG_FS_DP_123") (pintype "passive"))
    )
    (net (code "104") (name "/PA15") (class "Default")
      (node (ref "U1") (pin "138") (pinfunction "PA15/JTDI/TIM2_CH1/TIM2_ETR/SPI1_NSS/SPI3_NSS/I2S3_WS_138") (pintype "passive"))
    )
    (net (code "105") (name "/PB1") (class "Default")
      (node (ref "U1") (pin "57") (pinfunction "PB1/TIM1_CH3N/TIM3_CH4/TIM8_CH3N/LCD_R6/OTG_HS_ULPI_D2/ETH_MII_RXD3/ADC12_IN9_57") (pintype "passive"))
    )
    (net (code "106") (name "/PB2") (class "Default")
      (node (ref "U1") (pin "58") (pinfunction "PB2/BOOT1_58") (pintype "passive"))
    )
    (net (code "107") (name "/PB3") (class "Default")
      (node (ref "U1") (pin "161") (pinfunction "PB3/JTDO/TIM2_CH2/SPI1_SCK/SPI3_SCK/I2S3_CK_161") (pintype "passive"))
    )
    (net (code "108") (name "/PB4") (class "Default")
      (node (ref "U1") (pin "162") (pinfunction "PB4/NJTRST/TIM3_CH1/SPI1_MISO/SPI3_MISO/I2S3ext_SD_162") (pintype "passive"))
    )
    (net (code "109") (name "/PB6") (class "Default")
      (node (ref "U1") (pin "164") (pinfunction "PB6/TIM4_CH1/I2C1_SCL/U1_TX/CAN2_TX/FMC_SDNE1/DCMI_D5_164") (pintype "passive"))
    )
    (net (code "110") (name "/PB7") (class "Default")
      (node (ref "U1") (pin "165") (pinfunction "PB7/TIM4_CH2/I2C1_SDA/U1_RX/FMC_NL/DCMI_VSYNC_165") (pintype "passive"))
    )
    (net (code "111") (name "/PB10") (class "Default")
      (node (ref "U1") (pin "79") (pinfunction "PB10/TIM2_CH3/I2C2_SCL/SPI2_SCK/I2S2_CK/U3_TX/OTG_HS_ULPI_D3/ETH_MII_RX_ER/LCD_G4_79") (pintype "passive"))
    )
    (net (code "112") (name "/PB11") (class "Default")
      (node (ref "U1") (pin "80") (pinfunction "PB11/TIM2_CH4/I2C2_SDA/U3_RX/OTG_HS_ULPI_D4/ETH_MII_TX_EN/ETH_RMII_TX_EN/LCD_G5_80") (pintype "passive"))
    )
    (net (code "113") (name "/PB12") (class "Default")
      (node (ref "U1") (pin "92") (pinfunction "PB12/TIM1_BKIN/I2C2_SMBA/SPI2_NSS/I2S2_WS/U3_CK/CAN2_RX/OTG_HS_ULPI_D5/ETH_MII_TXD0/ETH_RMII_TXD0/OTG_HS_ID_92") (pintype "passive"))
    )
    (net (code "114") (name "/PB13") (class "Default")
      (node (ref "U1") (pin "93") (pinfunction "PB13/TIM1_CH1N/SPI2_SCK/I2S2_CK/U3_CTS/CAN2_TX/OTG_HS_ULPI_D6/ETH_MII_TXD1/ETH_RMII_TXD1/OTG_HS_VBUS_93") (pintype "passive"))
    )
    (net (code "115") (name "/PB14") (class "Default")
      (node (ref "U1") (pin "94") (pinfunction "PB14/TIM1_CH2N/TIM8_CH2N/SPI2_MISO/I2S2ext_SD/U3_RTS/TIM12_CH1/OTG_HS_DM_94") (pintype "passive"))
    )
    (net (code "116") (name "/PB15") (class "Default")
      (node (ref "U1") (pin "95") (pinfunction "PB15/RTC_REFIN/TIM1_CH3N/TIM8_CH3N/SPI2_MOSI/I2S2_SD/TIM12_CH2/OTG_HS_DP_95") (pintype "passive"))
    )
    (net (code "117") (name "/PC1") (class "Default")
      (node (ref "U1") (pin "33") (pinfunction "PC1/ETH_MDC/ADC123_IN11_33") (pintype "passive"))
    )
    (net (code "118") (name "/PC4") (class "Default")
      (node (ref "J1") (pin "38") (pinfunction "38_38") (pintype "passive"))
      (node (ref "LCD1") (pin "34") (pinfunction "CLK_34") (pintype "passive"))
      (node (ref "U1") (pin "54") (pinfunction "PC4/ETH_MII_RXD0/ETH_RMII_RXD0/ADC12_IN14_54") (pintype "passive"))
    )
    (net (code "119") (name "/PC5") (class "Default")
      (node (ref "J1") (pin "35") (pinfunction "35_35") (pintype "passive"))
      (node (ref "LCD1") (pin "33") (pinfunction "T_CS_33") (pintype "passive"))
      (node (ref "U1") (pin "55") (pinfunction "PC5/ETH_MII_RXD1/ETH_RMII_RXD1/ADC12_IN15_55") (pintype "passive"))
    )
    (net (code "120") (name "/PC6") (class "Default")
      (node (ref "U1") (pin "115") (pinfunction "PC6/TIM3_CH1/TIM8_CH1/I2S2_MCK/U6_TX/SDIO_D6/DCMI_D0/LCD_HSYNC_115") (pintype "passive"))
    )
    (net (code "121") (name "/PC7") (class "Default")
      (node (ref "U1") (pin "116") (pinfunction "PC7/TIM3_CH2/TIM8_CH2/I2S3_MCK/U6_RX/SDIO_D7/DCMI_D1/LCD_G6_116") (pintype "passive"))
    )
    (net (code "122") (name "/PC8") (class "Default")
      (node (ref "R15") (pin "1") (pintype "passive"))
      (node (ref "TF_CARD") (pin "7") (pinfunction "DAT0/DO_7") (pintype "passive"))
      (node (ref "U1") (pin "117") (pinfunction "PC8/TIM3_CH3/TIM8_CH3/U6_CK/SDIO_D0/DCMI_D2_117") (pintype "passive"))
    )
    (net (code "123") (name "/PC9") (class "Default")
      (node (ref "R19") (pin "1") (pintype "passive"))
      (node (ref "TF_CARD") (pin "8") (pinfunction "DAT1/IRQ_8") (pintype "passive"))
      (node (ref "U1") (pin "118") (pinfunction "PC9/MCO2/TIM3_CH4/TIM8_CH4/I2C3_SDA/I2S_CKIN/SDIO_D1/DCMI_D3_118") (pintype "passive"))
    )
    (net (code "124") (name "/PC10") (class "Default")
      (node (ref "R18") (pin "1") (pintype "passive"))
      (node (ref "TF_CARD") (pin "1") (pinfunction "DAT2/NC_1") (pintype "passive"))
      (node (ref "U1") (pin "139") (pinfunction "PC10/SPI3_SCK/I2S3_CK/U3_TX/U4_TX/SDIO_D2/DCMI_D8/LCD_R2_139") (pintype "passive"))
    )
    (net (code "125") (name "/PC11") (class "Default")
      (node (ref "R17") (pin "1") (pintype "passive"))
      (node (ref "TF_CARD") (pin "2") (pinfunction "CS/DATA3_2") (pintype "passive"))
      (node (ref "U1") (pin "140") (pinfunction "PC11/I2S3ext_SD/SPI3_MISO/U3_RX/U4_RX/SDIO_D3/DCMI_D4_140") (pintype "passive"))
    )
    (net (code "126") (name "/PC12") (class "Default")
      (node (ref "TF_CARD") (pin "5") (pinfunction "CLK_5") (pintype "passive"))
      (node (ref "U1") (pin "141") (pinfunction "PC12/SPI3_MOSI/I2S3_SD/U3_CK/U5_TX/SDIO_CK/DCMI_D9_141") (pintype "passive"))
    )
    (net (code "127") (name "/PC13") (class "Default")
      (node (ref "U1") (pin "8") (pinfunction "PC13/TAMP_1_8") (pintype "passive"))
    )
    (net (code "128") (name "/PC14") (class "Default")
      (node (ref "C3") (pin "2") (pintype "passive"))
      (node (ref "U1") (pin "9") (pinfunction "PC14/OSC32_IN_9") (pintype "passive"))
      (node (ref "Y2") (pin "2") (pinfunction "OSC2_2") (pintype "passive"))
    )
    (net (code "129") (name "/PC15") (class "Default")
      (node (ref "C4") (pin "2") (pintype "passive"))
      (node (ref "U1") (pin "10") (pinfunction "PC15/OSC32_OUT_10") (pintype "passive"))
      (node (ref "Y2") (pin "1") (pinfunction "OSC1_1") (pintype "passive"))
    )
    (net (code "130") (name "/PD2") (class "Default")
      (node (ref "R16") (pin "1") (pintype "passive"))
      (node (ref "TF_CARD") (pin "3") (pinfunction "CMD_3") (pintype "passive"))
      (node (ref "U1") (pin "144") (pinfunction "PD2/TIM3_ETR/U5_RX/SDIO_CMD/DCMI_D11_144") (pintype "passive"))
    )
    (net (code "131") (name "/PE2") (class "Default")
      (node (ref "U1") (pin "1") (pinfunction "PE2/SPI4_SCK/SAI1_MCLK_A/ETH_MII_TXD3/FMC_A23_1") (pintype "passive"))
      (node (ref "U2") (pin "11") (pinfunction "MCLK_11") (pintype "passive"))
    )
    (net (code "132") (name "/PE3") (class "Default")
      (node (ref "U1") (pin "2") (pinfunction "PE3/SAI1_SD_B/FMC_A19_2") (pintype "passive"))
      (node (ref "U2") (pin "9") (pinfunction "ADCDAT_9") (pintype "passive"))
    )
    (net (code "133") (name "/PE4") (class "Default")
      (node (ref "U1") (pin "3") (pinfunction "PE4/SPI4_NSS/SAI1_FS_A/FMC_A20/DCMI_D4/LCD_B0_3") (pintype "passive"))
      (node (ref "U2") (pin "7") (pinfunction "LRC_7") (pintype "passive"))
    )
    (net (code "134") (name "/PE5") (class "Default")
      (node (ref "U1") (pin "4") (pinfunction "PE5/TIM9_CH1/SPI4_MISO/SAI1_SCK_A/FMC_A21/DCMI_D6/LCD_G0_4") (pintype "passive"))
      (node (ref "U2") (pin "8") (pinfunction "BCLK_8") (pintype "passive"))
    )
    (net (code "135") (name "/PE6") (class "Default")
      (node (ref "U1") (pin "5") (pinfunction "PE6/TIM9_CH2/SPI4_MOSI/SAI1_SD_A/FMC_A22/DCMI_D7/LCD_G1_5") (pintype "passive"))
      (node (ref "U2") (pin "10") (pinfunction "DACDAT_10") (pintype "passive"))
    )
    (net (code "136") (name "/PG13") (class "Default")
      (node (ref "U1") (pin "156") (pinfunction "PG13/SPI6_SCK/U6_CTS/ETH_MII_TXD0/ETH_RMII_TXD0/FMC_A24_156") (pintype "passive"))
    )
    (net (code "137") (name "/PG14") (class "Default")
      (node (ref "U1") (pin "157") (pinfunction "PG14/SPI6_MOSI/U6_TX/ETH_MII_TXD1/ETH_RMII_TXD1/FMC_A25_157") (pintype "passive"))
    )
    (net (code "138") (name "/PH0") (class "Default")
      (node (ref "C1") (pin "1") (pintype "passive"))
      (node (ref "U1") (pin "29") (pinfunction "PH0/OSC_IN_29") (pintype "passive"))
      (node (ref "Y1") (pin "2") (pinfunction "OSC2_2") (pintype "passive"))
    )
    (net (code "139") (name "/PH1") (class "Default")
      (node (ref "C2") (pin "1") (pintype "passive"))
      (node (ref "U1") (pin "30") (pinfunction "PH1/OSC_OUT_30") (pintype "passive"))
      (node (ref "Y1") (pin "1") (pinfunction "OSC1_1") (pintype "passive"))
    )
    (net (code "140") (name "/PH2") (class "Default")
      (node (ref "U1") (pin "43") (pinfunction "PH2/ETH_MII_CRS/FMC_SDCKE0/LCD_R0_43") (pintype "passive"))
    )
    (net (code "141") (name "/PH3") (class "Default")
      (node (ref "U1") (pin "44") (pinfunction "PH3/ETH_MII_COL/FMC_SDNE0/LCD_R1_44") (pintype "passive"))
    )
    (net (code "142") (name "/PH6") (class "Default")
      (node (ref "U1") (pin "83") (pinfunction "PH6/I2C2_SMBA/SPI5_SCK/TIM12_CH1/ETH_MII_RXD2/FMC_SDNE1/DCMI_D8_83") (pintype "passive"))
    )
    (net (code "143") (name "/PH7") (class "Default")
      (node (ref "U1") (pin "84") (pinfunction "PH7/I2C3_SCL/SPI5_MISO/ETH_MII_RXD3/FMC_SDCKE1/DCMI_D9_84") (pintype "passive"))
    )
    (net (code "144") (name "/PH8") (class "Default")
      (node (ref "U1") (pin "85") (pinfunction "PH8/I2C3_SDA/FMC_D16/DCMI_HSYNC/LCD_R2_85") (pintype "passive"))
    )
    (net (code "145") (name "/PI11") (class "Default")
      (node (ref "U1") (pin "13") (pinfunction "PI11/OTG_HS_ULPI_DIR_13") (pintype "passive"))
    )
    (net (code "146") (name "/VUSB") (class "Default")
      (node (ref "POWER") (pin "2") (pinfunction "TAP_2") (pintype "passive"))
      (node (ref "USB_232") (pin "1") (pinfunction "VCC_1") (pintype "passive"))
      (node (ref "USB_SLAVE") (pin "1") (pinfunction "VCC_1") (pintype "passive"))
    )
    (net (code "147") (name "AGND") (class "Default")
      (node (ref "AUX") (pin "3") (pinfunction "COM_3") (pintype "passive"))
      (node (ref "C51") (pin "2") (pintype "passive"))
      (node (ref "C52") (pin "2") (pintype "passive"))
      (node (ref "C67") (pin "1") (pintype "passive"))
      (node (ref "C68") (pin "1") (pintype "passive"))
      (node (ref "C69") (pin "1") (pintype "passive"))
      (node (ref "MIC1") (pin "3") (pinfunction "COM_3") (pintype "passive"))
      (node (ref "PHONE") (pin "3") (pinfunction "COM_3") (pintype "passive"))
      (node (ref "R31") (pin "2") (pintype "passive"))
      (node (ref "R34") (pin "1") (pintype "passive"))
      (node (ref "R35") (pin "1") (pintype "passive"))
      (node (ref "U2") (pin "28") (pinfunction "AGND_28") (pintype "passive"))
    )
    (net (code "148") (name "GND") (class "Default")
      (node (ref "C1") (pin "2") (pintype "passive"))
      (node (ref "C10") (pin "1") (pintype "passive"))
      (node (ref "C11") (pin "1") (pintype "passive"))
      (node (ref "C12") (pin "1") (pintype "passive"))
      (node (ref "C13") (pin "1") (pintype "passive"))
      (node (ref "C14") (pin "1") (pintype "passive"))
      (node (ref "C15") (pin "1") (pintype "passive"))
      (node (ref "C16") (pin "1") (pintype "passive"))
      (node (ref "C17") (pin "1") (pintype "passive"))
      (node (ref "C18") (pin "1") (pintype "passive"))
      (node (ref "C19") (pin "1") (pintype "passive"))
      (node (ref "C2") (pin "2") (pintype "passive"))
      (node (ref "C20") (pin "1") (pintype "passive"))
      (node (ref "C21") (pin "1") (pintype "passive"))
      (node (ref "C22") (pin "1") (pintype "passive"))
      (node (ref "C23") (pin "1") (pintype "passive"))
      (node (ref "C24") (pin "1") (pintype "passive"))
      (node (ref "C25") (pin "1") (pintype "passive"))
      (node (ref "C26") (pin "1") (pintype "passive"))
      (node (ref "C27") (pin "1") (pintype "passive"))
      (node (ref "C28") (pin "1") (pintype "passive"))
      (node (ref "C29") (pin "1") (pintype "passive"))
      (node (ref "C3") (pin "1") (pintype "passive"))
      (node (ref "C30") (pin "2") (pintype "passive"))
      (node (ref "C31") (pin "2") (pintype "passive"))
      (node (ref "C32") (pin "2") (pintype "passive"))
      (node (ref "C33") (pin "1") (pintype "passive"))
      (node (ref "C34") (pin "1") (pintype "passive"))
      (node (ref "C35") (pin "2") (pinfunction "GND_2") (pintype "passive"))
      (node (ref "C36") (pin "2") (pintype "passive"))
      (node (ref "C38") (pin "2") (pintype "passive"))
      (node (ref "C39") (pin "2") (pintype "passive"))
      (node (ref "C4") (pin "1") (pintype "passive"))
      (node (ref "C40") (pin "1") (pintype "passive"))
      (node (ref "C41") (pin "1") (pintype "passive"))
      (node (ref "C42") (pin "1") (pintype "passive"))
      (node (ref "C43") (pin "1") (pintype "passive"))
      (node (ref "C44") (pin "1") (pintype "passive"))
      (node (ref "C45") (pin "1") (pintype "passive"))
      (node (ref "C46") (pin "1") (pintype "passive"))
      (node (ref "C47") (pin "1") (pintype "passive"))
      (node (ref "C48") (pin "1") (pintype "passive"))
      (node (ref "C49") (pin "2") (pintype "passive"))
      (node (ref "C5") (pin "1") (pintype "passive"))
      (node (ref "C50") (pin "1") (pintype "passive"))
      (node (ref "C55") (pin "1") (pintype "passive"))
      (node (ref "C56") (pin "1") (pintype "passive"))
      (node (ref "C57") (pin "1") (pintype "passive"))
      (node (ref "C58") (pin "1") (pintype "passive"))
      (node (ref "C6") (pin "1") (pintype "passive"))
      (node (ref "C7") (pin "1") (pintype "passive"))
      (node (ref "C70") (pin "1") (pintype "passive"))
      (node (ref "C8") (pin "1") (pintype "passive"))
      (node (ref "C9") (pin "1") (pintype "passive"))
      (node (ref "J1") (pin "11") (pinfunction "11_11") (pintype "passive"))
      (node (ref "J1") (pin "12") (pinfunction "12_12") (pintype "passive"))
      (node (ref "J1") (pin "13") (pinfunction "13_13") (pintype "passive"))
      (node (ref "J1") (pin "20") (pinfunction "20_20") (pintype "passive"))
      (node (ref "J1") (pin "21") (pinfunction "21_21") (pintype "passive"))
      (node (ref "J1") (pin "22") (pinfunction "22_22") (pintype "passive"))
      (node (ref "J1") (pin "23") (pinfunction "23_23") (pintype "passive"))
      (node (ref "J1") (pin "29") (pinfunction "29_29") (pintype "passive"))
      (node (ref "J1") (pin "3") (pinfunction "3_3") (pintype "passive"))
      (node (ref "J1") (pin "4") (pinfunction "4_4") (pintype "passive"))
      (node (ref "J1") (pin "5") (pinfunction "5_5") (pintype "passive"))
      (node (ref "LCD1") (pin "22") (pinfunction "GND_22") (pintype "passive"))
      (node (ref "LCD1") (pin "26") (pinfunction "GND_26") (pintype "passive"))
      (node (ref "LCD1") (pin "27") (pinfunction "GND_27") (pintype "passive"))
      (node (ref "P10") (pin "1") (pinfunction "1_1") (pintype "passive"))
      (node (ref "PWR") (pin "2") (pinfunction "K_2") (pintype "passive"))
      (node (ref "R1") (pin "2") (pintype "passive"))
      (node (ref "R28") (pin "1") (pintype "passive"))
      (node (ref "R31") (pin "1") (pintype "passive"))
      (node (ref "R32") (pin "1") (pintype "passive"))
      (node (ref "R8") (pin "2") (pintype "passive"))
      (node (ref "R9") (pin "2") (pintype "passive"))
      (node (ref "RST") (pin "2") (pinfunction "2_2") (pintype "passive"))
      (node (ref "TF_CARD") (pin "6") (pinfunction "VSS_6") (pintype "passive"))
      (node (ref "U1") (pin "102") (pinfunction "VSS_102") (pintype "passive"))
      (node (ref "U1") (pin "113") (pinfunction "VSS_113") (pintype "passive"))
      (node (ref "U1") (pin "126") (pinfunction "VSS_126") (pintype "passive"))
      (node (ref "U1") (pin "135") (pinfunction "VSS_135") (pintype "passive"))
      (node (ref "U1") (pin "14") (pinfunction "VSS_14") (pintype "passive"))
      (node (ref "U1") (pin "148") (pinfunction "VSS_148") (pintype "passive"))
      (node (ref "U1") (pin "158") (pinfunction "VSS_158") (pintype "passive"))
      (node (ref "U1") (pin "22") (pinfunction "VSS_22") (pintype "passive"))
      (node (ref "U1") (pin "37") (pinfunction "VSSA_37") (pintype "passive"))
      (node (ref "U1") (pin "61") (pinfunction "VSS_61") (pintype "passive"))
      (node (ref "U1") (pin "71") (pinfunction "VSS_71") (pintype "passive"))
      (node (ref "U1") (pin "90") (pinfunction "VSS_90") (pintype "passive"))
      (node (ref "U10") (pin "13") (pinfunction "VSS_13") (pintype "passive"))
      (node (ref "U10") (pin "36") (pinfunction "VSS_36") (pintype "passive"))
      (node (ref "U11") (pin "12") (pinfunction "VSSQ1_12") (pintype "power_in"))
      (node (ref "U11") (pin "28") (pinfunction "VSS2_28") (pintype "power_in"))
      (node (ref "U11") (pin "41") (pinfunction "VSS0_41") (pintype "power_in"))
      (node (ref "U11") (pin "46") (pinfunction "VSSQ2_46") (pintype "power_in"))
      (node (ref "U11") (pin "52") (pinfunction "VSSQ3_52") (pintype "power_in"))
      (node (ref "U11") (pin "54") (pinfunction "VSS1_54") (pintype "power_in"))
      (node (ref "U11") (pin "6") (pinfunction "VSSQ0_6") (pintype "power_in"))
      (node (ref "U12") (pin "1") (pinfunction "GND_1") (pintype "passive"))
      (node (ref "U14") (pin "1") (pinfunction "GND_1") (pintype "passive"))
      (node (ref "U2") (pin "12") (pinfunction "DGND_12") (pintype "passive"))
      (node (ref "U2") (pin "24") (pinfunction "SPKGND_24") (pintype "passive"))
      (node (ref "U2") (pin "33") (pinfunction "GNDPAD_33") (pintype "passive"))
      (node (ref "U3") (pin "1") (pinfunction "A0_1") (pintype "passive"))
      (node (ref "U3") (pin "2") (pinfunction "A1_2") (pintype "passive"))
      (node (ref "U3") (pin "3") (pinfunction "A2_3") (pintype "passive"))
      (node (ref "U3") (pin "4") (pinfunction "GND_4") (pintype "passive"))
      (node (ref "U3") (pin "7") (pinfunction "WP_7") (pintype "passive"))
      (node (ref "U4") (pin "4") (pinfunction "GND_4") (pintype "passive"))
      (node (ref "U6") (pin "3") (pinfunction "NC_3") (pintype "passive"))
      (node (ref "U6") (pin "4") (pinfunction "GND_4") (pintype "passive"))
      (node (ref "USB_232") (pin "5") (pinfunction "GND_5") (pintype "passive"))
      (node (ref "USB_SLAVE") (pin "5") (pinfunction "GND_5") (pintype "passive"))
    )
    (net (code "149") (name "Net-(AUX-CHL)") (class "Default")
      (node (ref "AUX") (pin "1") (pinfunction "CHL_1") (pintype "passive"))
      (node (ref "C66") (pin "2") (pintype "passive"))
    )
    (net (code "150") (name "Net-(AUX-CHR)") (class "Default")
      (node (ref "AUX") (pin "2") (pinfunction "CHR_2") (pintype "passive"))
      (node (ref "C65") (pin "2") (pintype "passive"))
    )
    (net (code "151") (name "Net-(C40-Pad2)") (class "Default")
      (node (ref "C40") (pin "2") (pintype "passive"))
      (node (ref "C41") (pin "2") (pintype "passive"))
      (node (ref "R20") (pin "1") (pintype "passive"))
      (node (ref "U10") (pin "12") (pinfunction "VCC_12") (pintype "passive"))
      (node (ref "U10") (pin "37") (pinfunction "VCC_37") (pintype "passive"))
    )
    (net (code "152") (name "Net-(C53-GND)") (class "Default")
      (node (ref "C53") (pin "2") (pinfunction "GND_2") (pintype "passive"))
      (node (ref "PHONE") (pin "2") (pinfunction "CHR_2") (pintype "passive"))
    )
    (net (code "153") (name "Net-(C53-VCC)") (class "Default")
      (node (ref "C53") (pin "1") (pinfunction "VCC_1") (pintype "passive"))
      (node (ref "U2") (pin "29") (pinfunction "ROUT1_29") (pintype "passive"))
    )
    (net (code "154") (name "Net-(C54-GND)") (class "Default")
      (node (ref "C54") (pin "2") (pinfunction "GND_2") (pintype "passive"))
      (node (ref "PHONE") (pin "1") (pinfunction "CHL_1") (pintype "passive"))
    )
    (net (code "155") (name "Net-(C54-VCC)") (class "Default")
      (node (ref "C54") (pin "1") (pinfunction "VCC_1") (pintype "passive"))
      (node (ref "U2") (pin "30") (pinfunction "LOUT1_30") (pintype "passive"))
    )
    (net (code "156") (name "Net-(DS0-A)") (class "Default")
      (node (ref "DS0") (pin "1") (pinfunction "A_1") (pintype "passive"))
      (node (ref "R37") (pin "1") (pintype "passive"))
    )
    (net (code "157") (name "Net-(DS1-A)") (class "Default")
      (node (ref "DS1") (pin "1") (pinfunction "A_1") (pintype "passive"))
      (node (ref "R38") (pin "1") (pintype "passive"))
    )
    (net (code "158") (name "Net-(MIC-GND)") (class "Default")
      (node (ref "C61") (pin "2") (pintype "passive"))
      (node (ref "C63") (pin "2") (pintype "passive"))
      (node (ref "C69") (pin "2") (pintype "passive"))
      (node (ref "MIC") (pin "2") (pinfunction "GND_2") (pintype "passive"))
      (node (ref "R33") (pin "2") (pintype "passive"))
      (node (ref "R34") (pin "2") (pintype "passive"))
    )
    (net (code "159") (name "Net-(MIC-VCC)") (class "Default")
      (node (ref "C62") (pin "2") (pintype "passive"))
      (node (ref "C64") (pin "2") (pintype "passive"))
      (node (ref "MIC") (pin "1") (pinfunction "VCC_1") (pintype "passive"))
      (node (ref "R35") (pin "2") (pintype "passive"))
    )
    (net (code "160") (name "Net-(MIC1-CHL)") (class "Default")
      (node (ref "C60") (pin "2") (pintype "passive"))
      (node (ref "MIC1") (pin "1") (pinfunction "CHL_1") (pintype "passive"))
    )
    (net (code "161") (name "Net-(MIC1-CHR)") (class "Default")
      (node (ref "C59") (pin "2") (pintype "passive"))
      (node (ref "MIC1") (pin "2") (pinfunction "CHR_2") (pintype "passive"))
    )
    (net (code "162") (name "Net-(PWR-A)") (class "Default")
      (node (ref "PWR") (pin "1") (pinfunction "A_1") (pintype "passive"))
      (node (ref "R39") (pin "1") (pintype "passive"))
    )
    (net (code "163") (name "Net-(U1-BYPASS_REG)") (class "Default")
      (node (ref "R1") (pin "1") (pintype "passive"))
      (node (ref "U1") (pin "48") (pinfunction "BYPASS_REG_48") (pintype "passive"))
    )
    (net (code "164") (name "Net-(U1-PDR_ON)") (class "Default")
      (node (ref "R5") (pin "1") (pintype "passive"))
      (node (ref "U1") (pin "171") (pinfunction "PDR_ON_171") (pintype "passive"))
    )
    (net (code "165") (name "Net-(U1-VBAT)") (class "Default")
      (node (ref "C8") (pin "2") (pintype "passive"))
      (node (ref "D1") (pin "2") (pintype "passive"))
      (node (ref "U1") (pin "6") (pinfunction "VBAT_6") (pintype "passive"))
    )
    (net (code "166") (name "Net-(U1-VCAP_1)") (class "Default")
      (node (ref "C6") (pin "2") (pintype "passive"))
      (node (ref "U1") (pin "81") (pinfunction "VCAP_1_81") (pintype "passive"))
    )
    (net (code "167") (name "Net-(U1-VCAP_2)") (class "Default")
      (node (ref "C7") (pin "2") (pintype "passive"))
      (node (ref "U1") (pin "125") (pinfunction "VCAP_2_125") (pintype "passive"))
    )
    (net (code "168") (name "Net-(U1-VDDA)") (class "Default")
      (node (ref "C11") (pin "2") (pintype "passive"))
      (node (ref "C12") (pin "2") (pintype "passive"))
      (node (ref "R3") (pin "1") (pintype "passive"))
      (node (ref "R4") (pin "1") (pintype "passive"))
      (node (ref "U1") (pin "39") (pinfunction "VDDA_39") (pintype "passive"))
    )
    (net (code "169") (name "Net-(U1-VREF+)") (class "Default")
      (node (ref "C10") (pin "2") (pintype "passive"))
      (node (ref "C9") (pin "2") (pintype "passive"))
      (node (ref "R3") (pin "2") (pintype "passive"))
      (node (ref "U1") (pin "38") (pinfunction "VREF+_38") (pintype "passive"))
    )
    (net (code "170") (name "Net-(U2-AUXL)") (class "Default")
      (node (ref "C65") (pin "1") (pintype "passive"))
      (node (ref "U2") (pin "19") (pinfunction "AUXL_19") (pintype "passive"))
    )
    (net (code "171") (name "Net-(U2-AUXR)") (class "Default")
      (node (ref "C66") (pin "1") (pintype "passive"))
      (node (ref "U2") (pin "20") (pinfunction "AUXR_20") (pintype "passive"))
    )
    (net (code "172") (name "Net-(U2-DBVDD)") (class "Default")
      (node (ref "C57") (pin "2") (pintype "passive"))
      (node (ref "C58") (pin "2") (pintype "passive"))
      (node (ref "R30") (pin "2") (pintype "passive"))
      (node (ref "U2") (pin "13") (pinfunction "DCVDD_13") (pintype "passive"))
      (node (ref "U2") (pin "14") (pinfunction "DBVDD_14") (pintype "passive"))
    )
    (net (code "173") (name "Net-(U2-L2{slash}GPIO2)") (class "Default")
      (node (ref "C59") (pin "1") (pintype "passive"))
      (node (ref "U2") (pin "3") (pinfunction "L2/GPIO2_3") (pintype "passive"))
    )
    (net (code "174") (name "Net-(U2-LIN)") (class "Default")
      (node (ref "C62") (pin "1") (pintype "passive"))
      (node (ref "U2") (pin "2") (pinfunction "LIN_2") (pintype "passive"))
    )
    (net (code "175") (name "Net-(U2-LIP)") (class "Default")
      (node (ref "C61") (pin "1") (pintype "passive"))
      (node (ref "U2") (pin "1") (pinfunction "LIP_1") (pintype "passive"))
    )
    (net (code "176") (name "Net-(U2-LOUT2)") (class "Default")
      (node (ref "SPK+") (pin "1") (pinfunction "1_1") (pintype "passive"))
      (node (ref "U2") (pin "25") (pinfunction "LOUT2_25") (pintype "passive"))
    )
    (net (code "177") (name "Net-(U2-MICBIAS)") (class "Default")
      (node (ref "C68") (pin "2") (pintype "passive"))
      (node (ref "R33") (pin "1") (pintype "passive"))
      (node (ref "U2") (pin "32") (pinfunction "MICBIAS_32") (pintype "passive"))
    )
    (net (code "178") (name "Net-(U2-MODE)") (class "Default")
      (node (ref "R32") (pin "2") (pintype "passive"))
      (node (ref "U2") (pin "18") (pinfunction "MODE_18") (pintype "passive"))
    )
    (net (code "179") (name "Net-(U2-R2{slash}GPIO3)") (class "Default")
      (node (ref "C60") (pin "1") (pintype "passive"))
      (node (ref "U2") (pin "6") (pinfunction "R2/GPIO3_6") (pintype "passive"))
    )
    (net (code "180") (name "Net-(U2-RIN)") (class "Default")
      (node (ref "C64") (pin "1") (pintype "passive"))
      (node (ref "U2") (pin "5") (pinfunction "RIN_5") (pintype "passive"))
    )
    (net (code "181") (name "Net-(U2-RIP)") (class "Default")
      (node (ref "C63") (pin "1") (pintype "passive"))
      (node (ref "U2") (pin "4") (pinfunction "RIP_4") (pintype "passive"))
    )
    (net (code "182") (name "Net-(U2-ROUT2)") (class "Default")
      (node (ref "SPK-") (pin "1") (pinfunction "1_1") (pintype "passive"))
      (node (ref "U2") (pin "23") (pinfunction "ROUT2_23") (pintype "passive"))
    )
    (net (code "183") (name "Net-(U2-SPKVDD)") (class "Default")
      (node (ref "C55") (pin "2") (pintype "passive"))
      (node (ref "C56") (pin "2") (pintype "passive"))
      (node (ref "R29") (pin "1") (pintype "passive"))
      (node (ref "U2") (pin "26") (pinfunction "SPKVDD_26") (pintype "passive"))
    )
    (net (code "184") (name "Net-(U2-VMID)") (class "Default")
      (node (ref "C67") (pin "2") (pintype "passive"))
      (node (ref "U2") (pin "27") (pinfunction "VMID_27") (pintype "passive"))
    )
    (net (code "185") (name "Net-(U10-~{WP})") (class "Default")
      (node (ref "R21") (pin "1") (pintype "passive"))
      (node (ref "U10") (pin "19") (pinfunction "~{WP}_19") (pintype "passive"))
    )
    (net (code "186") (name "Net-(U14-D+)") (class "Default")
      (node (ref "U14") (pin "5") (pinfunction "D+_5") (pintype "passive"))
      (node (ref "USB_232") (pin "3") (pinfunction "D+_3") (pintype "passive"))
    )
    (net (code "187") (name "Net-(U14-D-)") (class "Default")
      (node (ref "U14") (pin "6") (pinfunction "D-_6") (pintype "passive"))
      (node (ref "USB_232") (pin "2") (pinfunction "D-_2") (pintype "passive"))
    )
    (net (code "188") (name "Net-(U14-V3)") (class "Default")
      (node (ref "C28") (pin "2") (pintype "passive"))
      (node (ref "U14") (pin "4") (pinfunction "V3_4") (pintype "passive"))
    )
    (net (code "189") (name "Net-(U14-XI)") (class "Default")
      (node (ref "C29") (pin "2") (pintype "passive"))
      (node (ref "U14") (pin "7") (pinfunction "XI_7") (pintype "passive"))
      (node (ref "Y3") (pin "1") (pinfunction "OSC1_1") (pintype "passive"))
    )
    (net (code "190") (name "Net-(U14-XO)") (class "Default")
      (node (ref "C30") (pin "1") (pintype "passive"))
      (node (ref "U14") (pin "8") (pinfunction "XO_8") (pintype "passive"))
      (node (ref "Y3") (pin "2") (pinfunction "OSC2_2") (pintype "passive"))
    )
    (net (code "191") (name "Net-(USB_SLAVE-D+)") (class "Default")
      (node (ref "R13") (pin "1") (pintype "passive"))
      (node (ref "R14") (pin "1") (pintype "passive"))
      (node (ref "USB_SLAVE") (pin "3") (pinfunction "D+_3") (pintype "passive"))
    )
    (net (code "192") (name "Net-(USB_SLAVE-D-)") (class "Default")
      (node (ref "R12") (pin "1") (pintype "passive"))
      (node (ref "USB_SLAVE") (pin "2") (pinfunction "D-_2") (pintype "passive"))
    )
    (net (code "193") (name "VCC3.3") (class "Default")
      (node (ref "C13") (pin "2") (pintype "passive"))
      (node (ref "C14") (pin "2") (pintype "passive"))
      (node (ref "C15") (pin "2") (pintype "passive"))
      (node (ref "C16") (pin "2") (pintype "passive"))
      (node (ref "C17") (pin "2") (pintype "passive"))
      (node (ref "C18") (pin "2") (pintype "passive"))
      (node (ref "C19") (pin "2") (pintype "passive"))
      (node (ref "C20") (pin "2") (pintype "passive"))
      (node (ref "C21") (pin "2") (pintype "passive"))
      (node (ref "C22") (pin "2") (pintype "passive"))
      (node (ref "C23") (pin "2") (pintype "passive"))
      (node (ref "C24") (pin "2") (pintype "passive"))
      (node (ref "C25") (pin "2") (pintype "passive"))
      (node (ref "C26") (pin "2") (pintype "passive"))
      (node (ref "C27") (pin "2") (pintype "passive"))
      (node (ref "C34") (pin "2") (pintype "passive"))
      (node (ref "C35") (pin "1") (pinfunction "VCC_1") (pintype "passive"))
      (node (ref "C36") (pin "1") (pintype "passive"))
      (node (ref "C38") (pin "1") (pintype "passive"))
      (node (ref "C39") (pin "1") (pintype "passive"))
      (node (ref "C42") (pin "2") (pintype "passive"))
      (node (ref "C43") (pin "2") (pintype "passive"))
      (node (ref "C44") (pin "2") (pintype "passive"))
      (node (ref "C45") (pin "2") (pintype "passive"))
      (node (ref "C46") (pin "2") (pintype "passive"))
      (node (ref "C47") (pin "2") (pintype "passive"))
      (node (ref "C48") (pin "2") (pintype "passive"))
      (node (ref "C49") (pin "1") (pintype "passive"))
      (node (ref "C51") (pin "1") (pintype "passive"))
      (node (ref "C52") (pin "1") (pintype "passive"))
      (node (ref "C70") (pin "2") (pintype "passive"))
      (node (ref "D1") (pin "1") (pintype "passive"))
      (node (ref "LCD1") (pin "24") (pinfunction "VDD3.3_24") (pintype "passive"))
      (node (ref "LCD1") (pin "25") (pinfunction "VDD3.3_25") (pintype "passive"))
      (node (ref "R10") (pin "2") (pintype "passive"))
      (node (ref "R11") (pin "2") (pintype "passive"))
      (node (ref "R13") (pin "2") (pintype "passive"))
      (node (ref "R15") (pin "2") (pintype "passive"))
      (node (ref "R16") (pin "2") (pintype "passive"))
      (node (ref "R17") (pin "2") (pintype "passive"))
      (node (ref "R18") (pin "2") (pintype "passive"))
      (node (ref "R19") (pin "2") (pintype "passive"))
      (node (ref "R2") (pin "1") (pintype "passive"))
      (node (ref "R20") (pin "2") (pintype "passive"))
      (node (ref "R21") (pin "2") (pintype "passive"))
      (node (ref "R22") (pin "1") (pintype "passive"))
      (node (ref "R30") (pin "1") (pintype "passive"))
      (node (ref "R36") (pin "1") (pintype "passive"))
      (node (ref "R37") (pin "2") (pintype "passive"))
      (node (ref "R38") (pin "2") (pintype "passive"))
      (node (ref "R39") (pin "2") (pintype "passive"))
      (node (ref "R4") (pin "2") (pintype "passive"))
      (node (ref "R40") (pin "2") (pintype "passive"))
      (node (ref "R5") (pin "2") (pintype "passive"))
      (node (ref "TF_CARD") (pin "4") (pinfunction "VDD_4") (pintype "passive"))
      (node (ref "U1") (pin "103") (pinfunction "VDD_103") (pintype "passive"))
      (node (ref "U1") (pin "114") (pinfunction "VDD_114") (pintype "passive"))
      (node (ref "U1") (pin "127") (pinfunction "VDD_127") (pintype "passive"))
      (node (ref "U1") (pin "136") (pinfunction "VDD_136") (pintype "passive"))
      (node (ref "U1") (pin "149") (pinfunction "VDD_149") (pintype "passive"))
      (node (ref "U1") (pin "15") (pinfunction "VDD_15") (pintype "passive"))
      (node (ref "U1") (pin "159") (pinfunction "VDD_159") (pintype "passive"))
      (node (ref "U1") (pin "172") (pinfunction "VDD_172") (pintype "passive"))
      (node (ref "U1") (pin "23") (pinfunction "VDD_23") (pintype "passive"))
      (node (ref "U1") (pin "36") (pinfunction "VDD_36") (pintype "passive"))
      (node (ref "U1") (pin "49") (pinfunction "VDD_49") (pintype "passive"))
      (node (ref "U1") (pin "62") (pinfunction "VDD_62") (pintype "passive"))
      (node (ref "U1") (pin "72") (pinfunction "VDD_72") (pintype "passive"))
      (node (ref "U1") (pin "82") (pinfunction "VDD_82") (pintype "passive"))
      (node (ref "U1") (pin "91") (pinfunction "VDD_91") (pintype "passive"))
      (node (ref "U11") (pin "1") (pinfunction "VDD0_1") (pintype "power_in"))
      (node (ref "U11") (pin "14") (pinfunction "VDD1_14") (pintype "power_in"))
      (node (ref "U11") (pin "27") (pinfunction "VDD2_27") (pintype "power_in"))
      (node (ref "U11") (pin "3") (pinfunction "VDDQ0_3") (pintype "power_in"))
      (node (ref "U11") (pin "43") (pinfunction "VDDQ2_43") (pintype "power_in"))
      (node (ref "U11") (pin "49") (pinfunction "VDDQ3_49") (pintype "power_in"))
      (node (ref "U11") (pin "9") (pinfunction "VDDQ1_9") (pintype "power_in"))
      (node (ref "U12") (pin "2") (pinfunction "OUT_2") (pintype "passive"))
      (node (ref "U12") (pin "4") (pinfunction "OUT_4") (pintype "passive"))
      (node (ref "U2") (pin "31") (pinfunction "AVDD_31") (pintype "passive"))
      (node (ref "U3") (pin "8") (pinfunction "VCC1_8") (pintype "passive"))
      (node (ref "U4") (pin "3") (pinfunction "WP#_3") (pintype "passive"))
      (node (ref "U4") (pin "7") (pinfunction "HOLD_7") (pintype "passive"))
      (node (ref "U4") (pin "8") (pinfunction "VCC_8") (pintype "passive"))
      (node (ref "U6") (pin "1") (pinfunction "VCC_1") (pintype "passive"))
    )
    (net (code "194") (name "VCC5") (class "Default")
      (node (ref "C31") (pin "1") (pintype "passive"))
      (node (ref "C32") (pin "1") (pintype "passive"))
      (node (ref "C33") (pin "2") (pintype "passive"))
      (node (ref "C50") (pin "2") (pintype "passive"))
      (node (ref "J1") (pin "1") (pinfunction "1_1") (pintype "passive"))
      (node (ref "J1") (pin "2") (pinfunction "2_2") (pintype "passive"))
      (node (ref "LCD1") (pin "28") (pinfunction "BL_VDD_28") (pintype "passive"))
      (node (ref "POWER") (pin "1") (pinfunction "I/O_1") (pintype "passive"))
      (node (ref "R29") (pin "2") (pintype "passive"))
      (node (ref "U12") (pin "3") (pinfunction "IN_3") (pintype "passive"))
      (node (ref "U14") (pin "16") (pinfunction "VCC_16") (pintype "passive"))
    )
    (net (code "195") (name "unconnected-(J1-PadA)") (class "Default")
      (node (ref "J1") (pin "A") (pinfunction "A_A") (pintype "passive"))
    )
    (net (code "196") (name "unconnected-(J1-PadB)") (class "Default")
      (node (ref "J1") (pin "B") (pinfunction "B_B") (pintype "passive"))
    )
    (net (code "197") (name "unconnected-(LCD1-MO-Pad32)") (class "Default")
      (node (ref "LCD1") (pin "32") (pinfunction "MO_32") (pintype "passive"))
    )
    (net (code "198") (name "unconnected-(POWER-GND-Pad4)") (class "Default")
      (node (ref "POWER") (pin "4") (pinfunction "GND_4") (pintype "passive"))
    )
    (net (code "199") (name "unconnected-(POWER-GND-Pad5)") (class "Default")
      (node (ref "POWER") (pin "5") (pinfunction "GND_5") (pintype "passive"))
    )
    (net (code "200") (name "unconnected-(POWER-I{slash}O-Pad3)") (class "Default")
      (node (ref "POWER") (pin "3") (pinfunction "I/O_3") (pintype "passive"))
    )
    (net (code "201") (name "unconnected-(U2-CSB{slash}GPIO1-Pad15)") (class "Default")
      (node (ref "U2") (pin "15") (pinfunction "CSB/GPIO1_15") (pintype "passive"))
    )
    (net (code "202") (name "unconnected-(U2-OUT3-Pad22)") (class "Default")
      (node (ref "U2") (pin "22") (pinfunction "OUT3_22") (pintype "passive"))
    )
    (net (code "203") (name "unconnected-(U2-OUT4-Pad21)") (class "Default")
      (node (ref "U2") (pin "21") (pinfunction "OUT4_21") (pintype "passive"))
    )
    (net (code "204") (name "unconnected-(U14-CTS#-Pad9)") (class "Default")
      (node (ref "U14") (pin "9") (pinfunction "CTS#_9") (pintype "passive"))
    )
    (net (code "205") (name "unconnected-(U14-DCD#-Pad12)") (class "Default")
      (node (ref "U14") (pin "12") (pinfunction "DCD#_12") (pintype "passive"))
    )
    (net (code "206") (name "unconnected-(U14-DSR#-Pad10)") (class "Default")
      (node (ref "U14") (pin "10") (pinfunction "DSR#_10") (pintype "passive"))
    )
    (net (code "207") (name "unconnected-(U14-DTR#-Pad13)") (class "Default")
      (node (ref "U14") (pin "13") (pinfunction "DTR#_13") (pintype "passive"))
    )
    (net (code "208") (name "unconnected-(U14-R232-Pad15)") (class "Default")
      (node (ref "U14") (pin "15") (pinfunction "R232_15") (pintype "passive"))
    )
    (net (code "209") (name "unconnected-(U14-RI#-Pad11)") (class "Default")
      (node (ref "U14") (pin "11") (pinfunction "RI#_11") (pintype "passive"))
    )
    (net (code "210") (name "unconnected-(U14-RTS#-Pad14)") (class "Default")
      (node (ref "U14") (pin "14") (pinfunction "RTS#_14") (pintype "passive"))
    )
    (net (code "211") (name "unconnected-(USB_232-NC-Pad4)") (class "Default")
      (node (ref "USB_232") (pin "4") (pinfunction "NC_4") (pintype "passive"))
    )
    (net (code "212") (name "unconnected-(USB_SLAVE-NC-Pad4)") (class "Default")
      (node (ref "USB_SLAVE") (pin "4") (pinfunction "NC_4") (pintype "passive"))
    )
  )
)
